# BasePCB.net
KiCad netlist of a schematic drawn in EAGLE
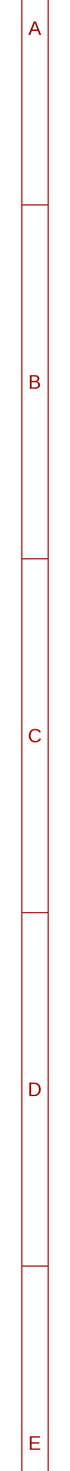
[diagram p0: schematic, sheet 1, part 1 of 2]
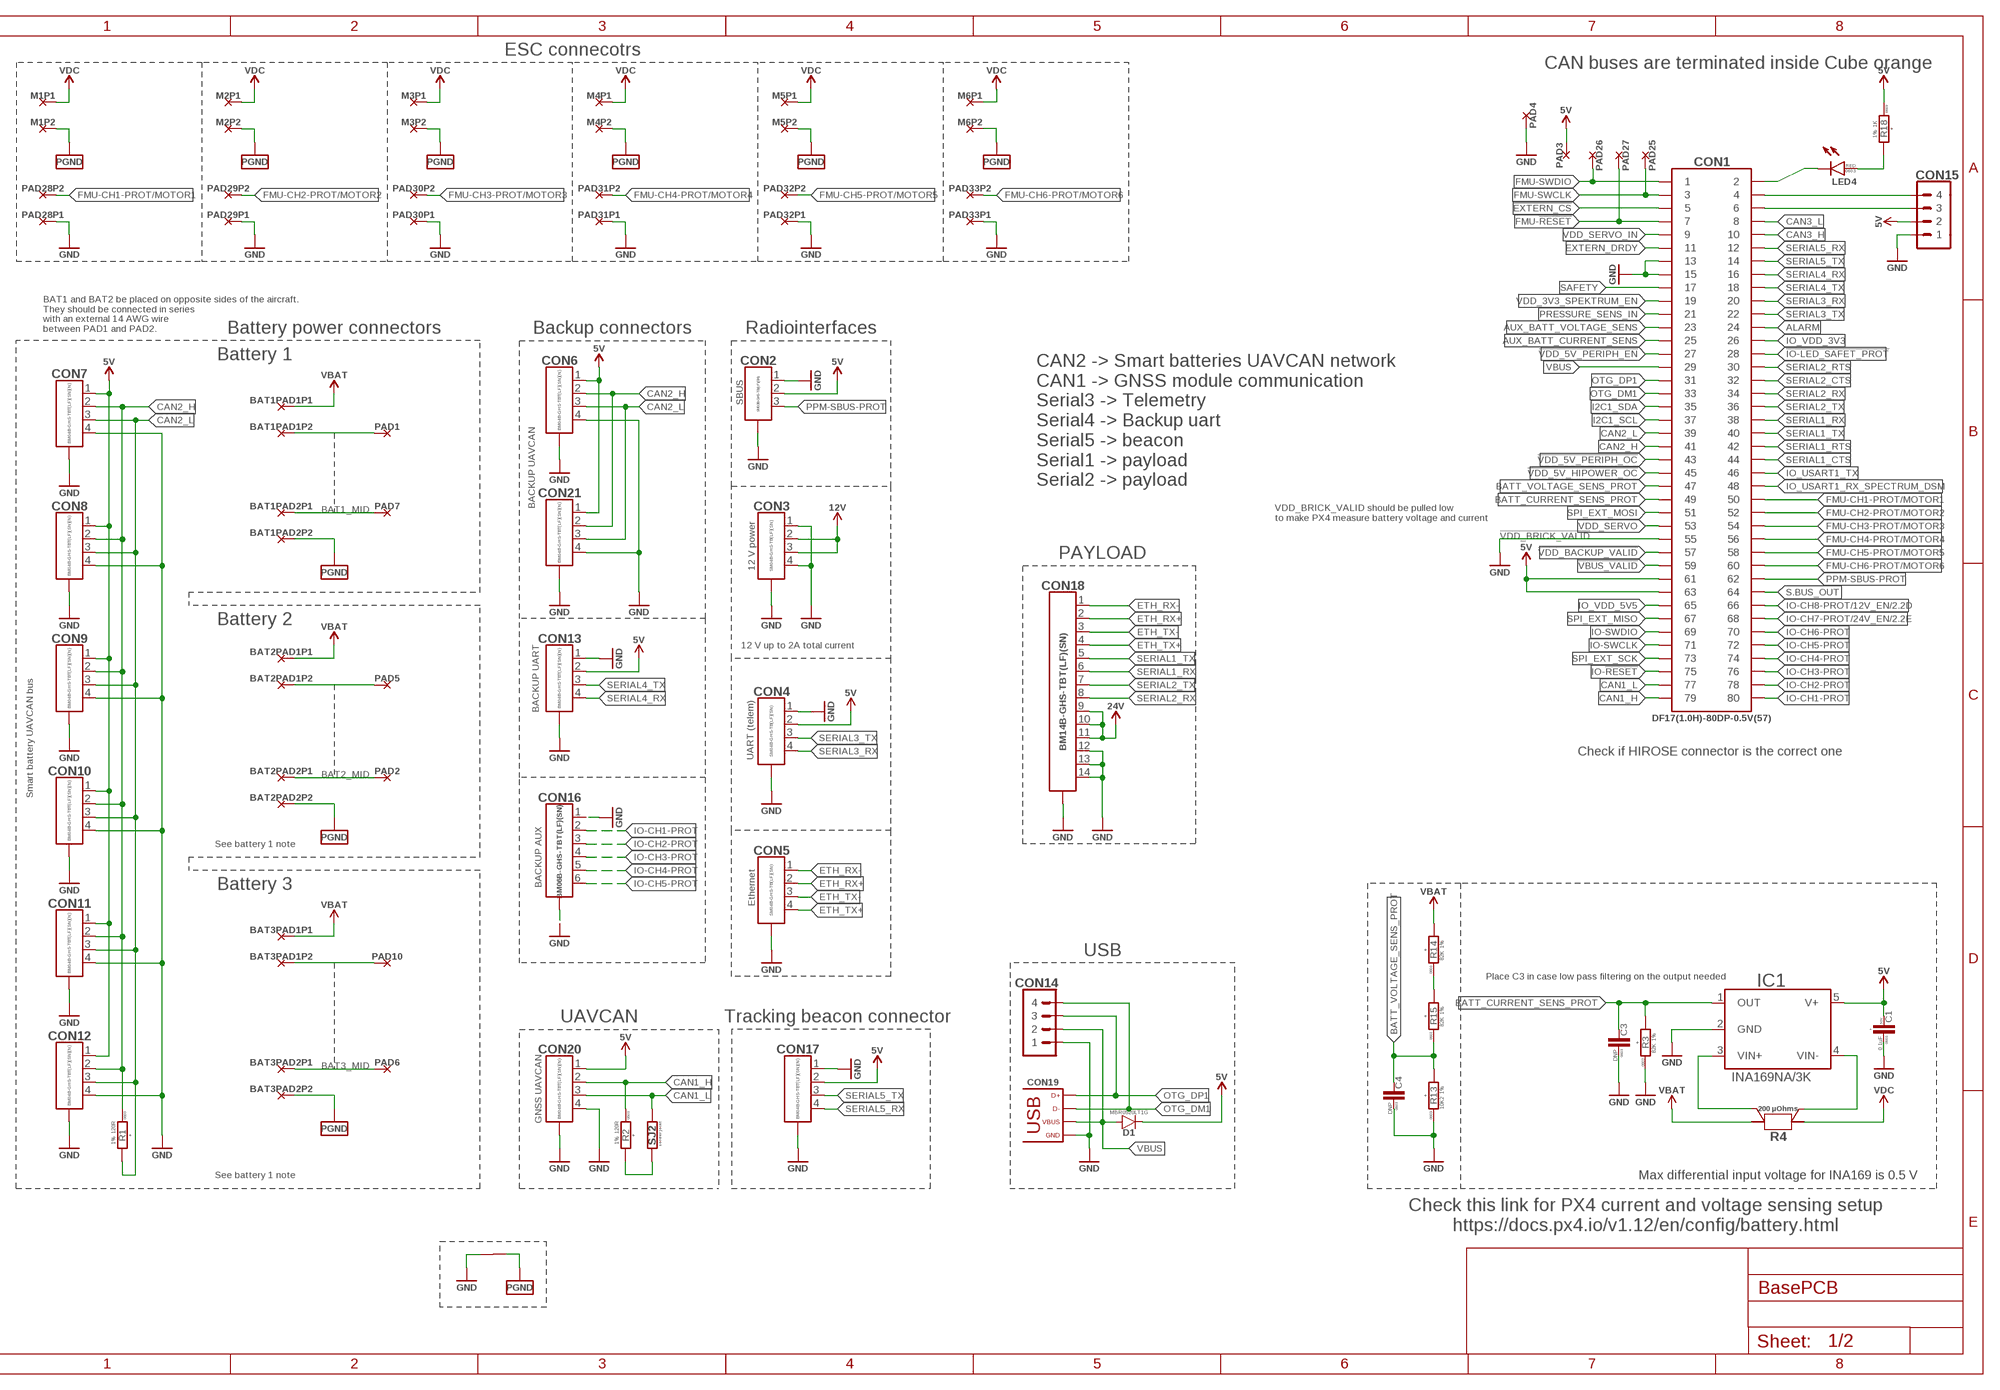
[diagram p1: schematic, sheet 1, part 2 of 2]
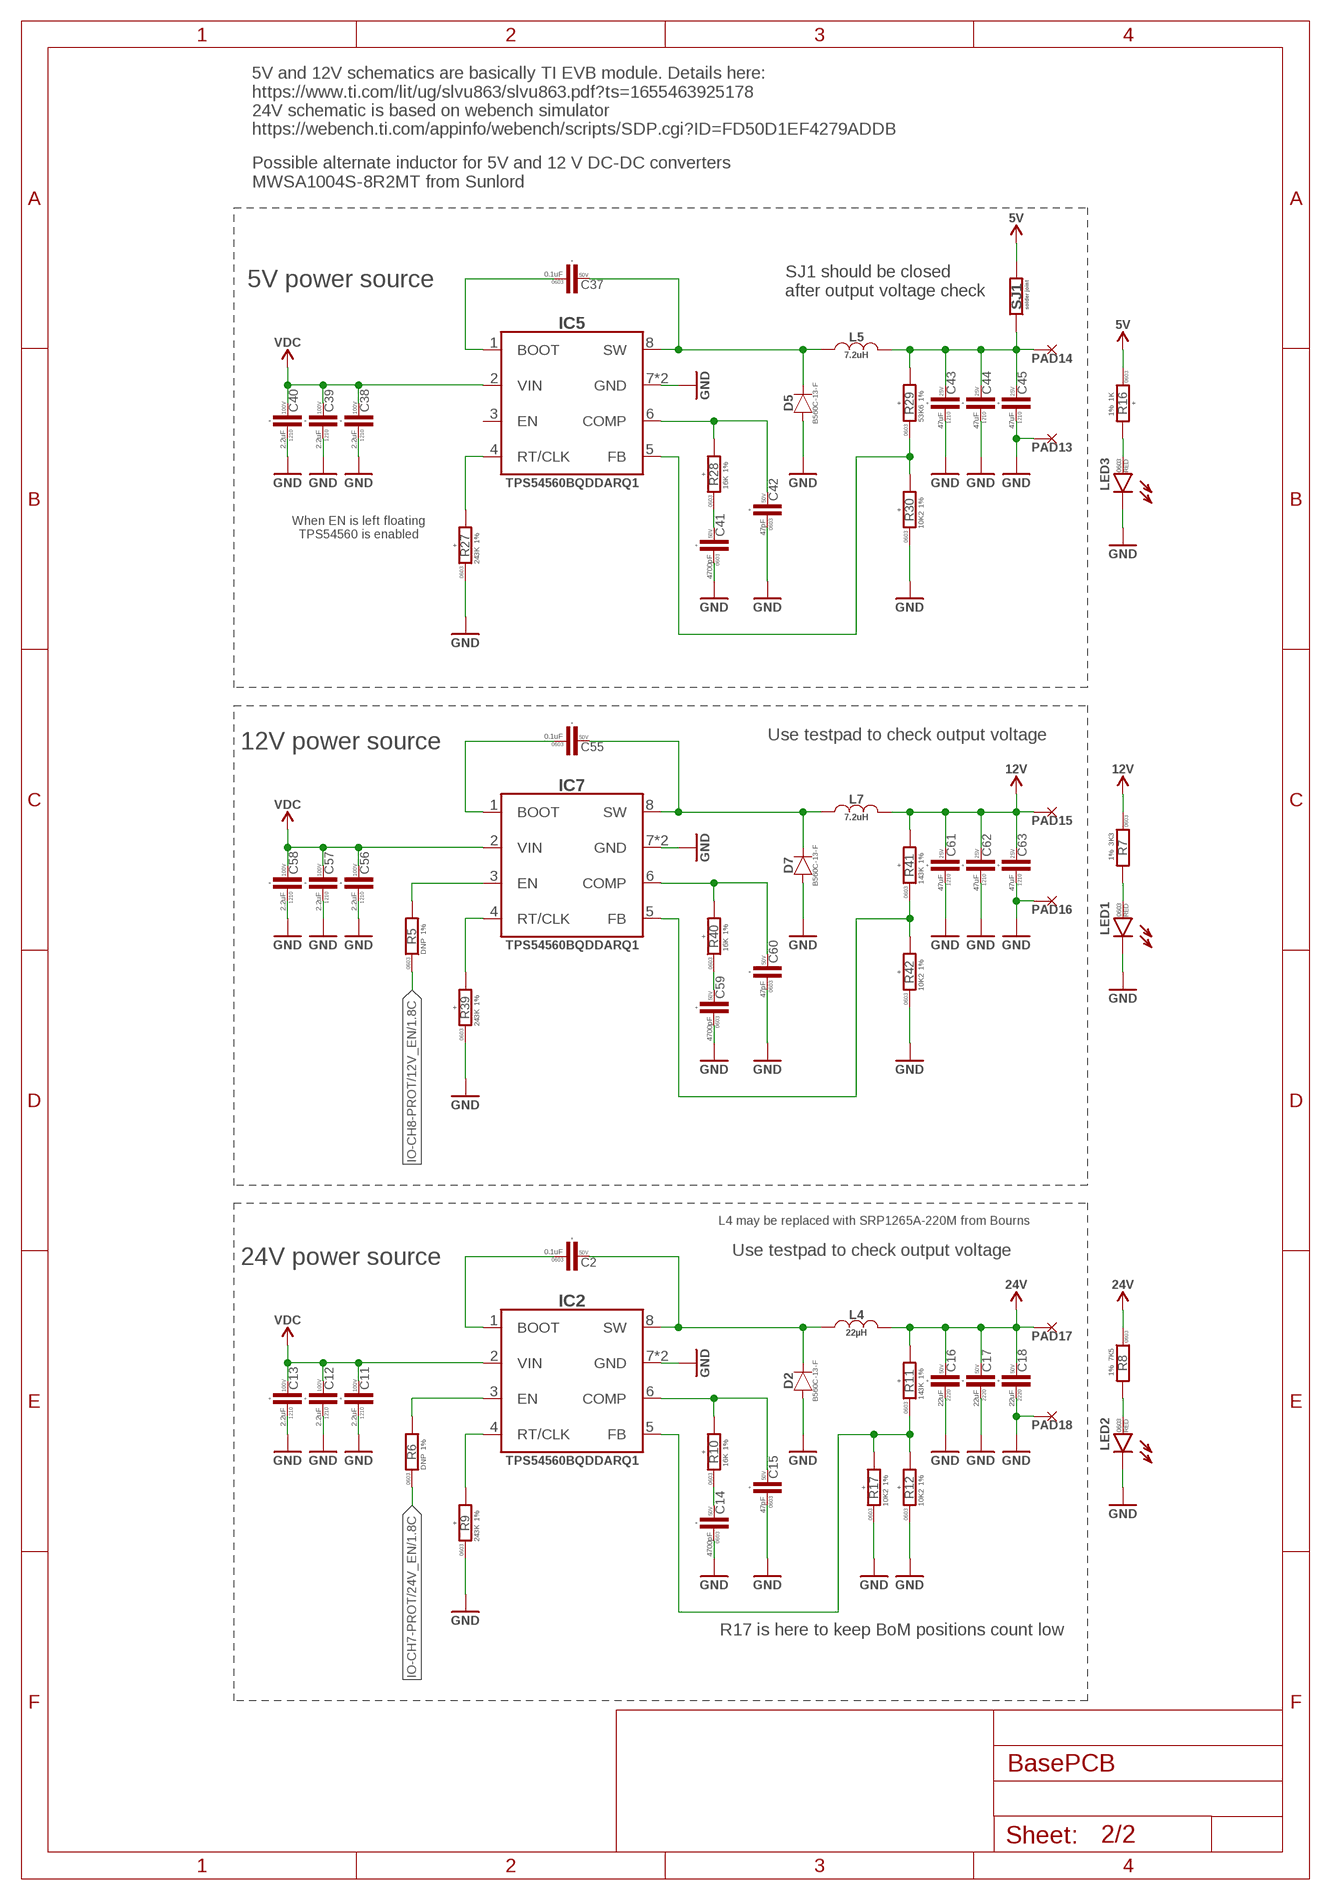
[diagram p2: schematic, sheet 2]

(export (version "E")
  (design (tool "Eeschema 10.0.6"))
  (components
    (comp (ref "C2")
      (value "0.1uF")
      (footprint "eagle-import:C0603")
      (fields
        (field (name "PACKAGE") "0603")
        (field (name "ALLOCATED") "+")
        (field (name "LCSC#") "C14663")
        (field (name "MANF") "YAGEO")
        (field (name "MANF#") "CC0603KRX7R9BB104")
        (field (name "VOLTAGE") "50V")
      )
      (libsource (lib "eagle-import") (part "C-0603"))
    )
    (comp (ref "C11")
      (value "2.2uF")
      (footprint "eagle-import:C1210")
      (fields
        (field (name "PACKAGE") "1210")
        (field (name "ALLOCATED") "+")
        (field (name "LCSC#") "C55151")
        (field (name "MANF") "Samsung Electro-Mechanics")
        (field (name "MANF#") "CL32B225KCJSNNE")
        (field (name "VOLTAGE") "100V")
      )
      (libsource (lib "eagle-import") (part "C-1210"))
    )
    (comp (ref "C12")
      (value "2.2uF")
      (footprint "eagle-import:C1210")
      (fields
        (field (name "PACKAGE") "1210")
        (field (name "ALLOCATED") "+")
        (field (name "LCSC#") "C55151")
        (field (name "MANF") "Samsung Electro-Mechanics")
        (field (name "MANF#") "CL32B225KCJSNNE")
        (field (name "VOLTAGE") "100V")
      )
      (libsource (lib "eagle-import") (part "C-1210"))
    )
    (comp (ref "C13")
      (value "2.2uF")
      (footprint "eagle-import:C1210")
      (fields
        (field (name "PACKAGE") "1210")
        (field (name "ALLOCATED") "+")
        (field (name "LCSC#") "C55151")
        (field (name "MANF") "Samsung Electro-Mechanics")
        (field (name "MANF#") "CL32B225KCJSNNE")
        (field (name "VOLTAGE") "100V")
      )
      (libsource (lib "eagle-import") (part "C-1210"))
    )
    (comp (ref "C14")
      (value "4700pF")
      (footprint "eagle-import:C0603")
      (fields
        (field (name "PACKAGE") "0603")
        (field (name "ALLOCATED") "+")
        (field (name "LCSC#") "C53987")
        (field (name "MANF") "FH(Guangdong Fenghua Advanced Tech)")
        (field (name "MANF#") "0603B472K500NT")
        (field (name "VOLTAGE") "50V")
      )
      (libsource (lib "eagle-import") (part "C-0603"))
    )
    (comp (ref "C15")
      (value "47pF")
      (footprint "eagle-import:C0603")
      (fields
        (field (name "PACKAGE") "0603")
        (field (name "ALLOCATED") "+")
        (field (name "LCSC#") "C1671")
        (field (name "MANF") "Samsung Electro-Mechanics")
        (field (name "MANF#") "CL10C470JB8NNNC")
        (field (name "VOLTAGE") "50V")
      )
      (libsource (lib "eagle-import") (part "C-0603"))
    )
    (comp (ref "C16")
      (value "22uF")
      (footprint "eagle-import:C2220")
      (fields
        (field (name "PACKAGE") "2220")
        (field (name "ALLOCATED") "+")
        (field (name "LCSC#") "C784103")
        (field (name "MANF") "PSA(Prosperity Dielectrics)")
        (field (name "MANF#") "FS55X226K500EHG")
        (field (name "VOLTAGE") "50V")
      )
      (libsource (lib "eagle-import") (part "C-C2220"))
    )
    (comp (ref "C17")
      (value "22uF")
      (footprint "eagle-import:C2220")
      (fields
        (field (name "PACKAGE") "2220")
        (field (name "ALLOCATED") "+")
        (field (name "LCSC#") "C784103")
        (field (name "MANF") "PSA(Prosperity Dielectrics)")
        (field (name "MANF#") "FS55X226K500EHG")
        (field (name "VOLTAGE") "50V")
      )
      (libsource (lib "eagle-import") (part "C-C2220"))
    )
    (comp (ref "C18")
      (value "22uF")
      (footprint "eagle-import:C2220")
      (fields
        (field (name "PACKAGE") "2220")
        (field (name "ALLOCATED") "+")
        (field (name "LCSC#") "C784103")
        (field (name "MANF") "PSA(Prosperity Dielectrics)")
        (field (name "MANF#") "FS55X226K500EHG")
        (field (name "VOLTAGE") "50V")
      )
      (libsource (lib "eagle-import") (part "C-C2220"))
    )
    (comp (ref "C37")
      (value "0.1uF")
      (footprint "eagle-import:C0603")
      (fields
        (field (name "PACKAGE") "0603")
        (field (name "ALLOCATED") "+")
        (field (name "LCSC#") "C14663")
        (field (name "MANF") "YAGEO")
        (field (name "MANF#") "CC0603KRX7R9BB104")
        (field (name "VOLTAGE") "50V")
      )
      (libsource (lib "eagle-import") (part "C-0603"))
    )
    (comp (ref "C38")
      (value "2.2uF")
      (footprint "eagle-import:C1210")
      (fields
        (field (name "PACKAGE") "1210")
        (field (name "ALLOCATED") "+")
        (field (name "LCSC#") "C55151")
        (field (name "MANF") "Samsung Electro-Mechanics")
        (field (name "MANF#") "CL32B225KCJSNNE")
        (field (name "VOLTAGE") "100V")
      )
      (libsource (lib "eagle-import") (part "C-1210"))
    )
    (comp (ref "C39")
      (value "2.2uF")
      (footprint "eagle-import:C1210")
      (fields
        (field (name "PACKAGE") "1210")
        (field (name "ALLOCATED") "+")
        (field (name "LCSC#") "C55151")
        (field (name "MANF") "Samsung Electro-Mechanics")
        (field (name "MANF#") "CL32B225KCJSNNE")
        (field (name "VOLTAGE") "100V")
      )
      (libsource (lib "eagle-import") (part "C-1210"))
    )
    (comp (ref "C40")
      (value "2.2uF")
      (footprint "eagle-import:C1210")
      (fields
        (field (name "PACKAGE") "1210")
        (field (name "ALLOCATED") "+")
        (field (name "LCSC#") "C55151")
        (field (name "MANF") "Samsung Electro-Mechanics")
        (field (name "MANF#") "CL32B225KCJSNNE")
        (field (name "VOLTAGE") "100V")
      )
      (libsource (lib "eagle-import") (part "C-1210"))
    )
    (comp (ref "C41")
      (value "4700pF")
      (footprint "eagle-import:C0603")
      (fields
        (field (name "PACKAGE") "0603")
        (field (name "ALLOCATED") "+")
        (field (name "LCSC#") "C53987")
        (field (name "MANF") "FH(Guangdong Fenghua Advanced Tech)")
        (field (name "MANF#") "0603B472K500NT")
        (field (name "VOLTAGE") "50V")
      )
      (libsource (lib "eagle-import") (part "C-0603"))
    )
    (comp (ref "C42")
      (value "47pF")
      (footprint "eagle-import:C0603")
      (fields
        (field (name "PACKAGE") "0603")
        (field (name "ALLOCATED") "+")
        (field (name "LCSC#") "C1671")
        (field (name "MANF") "Samsung Electro-Mechanics")
        (field (name "MANF#") "CL10C470JB8NNNC")
        (field (name "VOLTAGE") "50V")
      )
      (libsource (lib "eagle-import") (part "C-0603"))
    )
    (comp (ref "C43")
      (value "47uF")
      (footprint "eagle-import:C1210")
      (fields
        (field (name "PACKAGE") "1210")
        (field (name "ALLOCATED") "+")
        (field (name "LCSC#") "C90142")
        (field (name "MANF") "Taiyo Yuden")
        (field (name "MANF#") "TMK325ABJ476MM-P")
        (field (name "VOLTAGE") "25V")
      )
      (libsource (lib "eagle-import") (part "C-1210"))
    )
    (comp (ref "C44")
      (value "47uF")
      (footprint "eagle-import:C1210")
      (fields
        (field (name "PACKAGE") "1210")
        (field (name "ALLOCATED") "+")
        (field (name "LCSC#") "C90142")
        (field (name "MANF") "Taiyo Yuden")
        (field (name "MANF#") "TMK325ABJ476MM-P")
        (field (name "VOLTAGE") "25V")
      )
      (libsource (lib "eagle-import") (part "C-1210"))
    )
    (comp (ref "C45")
      (value "47uF")
      (footprint "eagle-import:C1210")
      (fields
        (field (name "PACKAGE") "1210")
        (field (name "ALLOCATED") "+")
        (field (name "LCSC#") "C90142")
        (field (name "MANF") "Taiyo Yuden")
        (field (name "MANF#") "TMK325ABJ476MM-P")
        (field (name "VOLTAGE") "25V")
      )
      (libsource (lib "eagle-import") (part "C-1210"))
    )
    (comp (ref "C55")
      (value "0.1uF")
      (footprint "eagle-import:C0603")
      (fields
        (field (name "PACKAGE") "0603")
        (field (name "ALLOCATED") "+")
        (field (name "LCSC#") "C14663")
        (field (name "MANF") "YAGEO")
        (field (name "MANF#") "CC0603KRX7R9BB104")
        (field (name "VOLTAGE") "50V")
      )
      (libsource (lib "eagle-import") (part "C-0603"))
    )
    (comp (ref "C56")
      (value "2.2uF")
      (footprint "eagle-import:C1210")
      (fields
        (field (name "PACKAGE") "1210")
        (field (name "ALLOCATED") "+")
        (field (name "LCSC#") "C55151")
        (field (name "MANF") "Samsung Electro-Mechanics")
        (field (name "MANF#") "CL32B225KCJSNNE")
        (field (name "VOLTAGE") "100V")
      )
      (libsource (lib "eagle-import") (part "C-1210"))
    )
    (comp (ref "C57")
      (value "2.2uF")
      (footprint "eagle-import:C1210")
      (fields
        (field (name "PACKAGE") "1210")
        (field (name "ALLOCATED") "+")
        (field (name "LCSC#") "C55151")
        (field (name "MANF") "Samsung Electro-Mechanics")
        (field (name "MANF#") "CL32B225KCJSNNE")
        (field (name "VOLTAGE") "100V")
      )
      (libsource (lib "eagle-import") (part "C-1210"))
    )
    (comp (ref "C58")
      (value "2.2uF")
      (footprint "eagle-import:C1210")
      (fields
        (field (name "PACKAGE") "1210")
        (field (name "ALLOCATED") "+")
        (field (name "LCSC#") "C55151")
        (field (name "MANF") "Samsung Electro-Mechanics")
        (field (name "MANF#") "CL32B225KCJSNNE")
        (field (name "VOLTAGE") "100V")
      )
      (libsource (lib "eagle-import") (part "C-1210"))
    )
    (comp (ref "C59")
      (value "4700pF")
      (footprint "eagle-import:C0603")
      (fields
        (field (name "PACKAGE") "0603")
        (field (name "ALLOCATED") "+")
        (field (name "LCSC#") "C53987")
        (field (name "MANF") "FH(Guangdong Fenghua Advanced Tech)")
        (field (name "MANF#") "0603B472K500NT")
        (field (name "VOLTAGE") "50V")
      )
      (libsource (lib "eagle-import") (part "C-0603"))
    )
    (comp (ref "C60")
      (value "47pF")
      (footprint "eagle-import:C0603")
      (fields
        (field (name "PACKAGE") "0603")
        (field (name "ALLOCATED") "+")
        (field (name "LCSC#") "C1620")
        (field (name "MANF") "FH(Guangdong Fenghua Advanced Tech)")
        (field (name "MANF#") "0603B471K500NT")
        (field (name "VOLTAGE") "50V")
      )
      (libsource (lib "eagle-import") (part "C-0603"))
    )
    (comp (ref "C61")
      (value "47uF")
      (footprint "eagle-import:C1210")
      (fields
        (field (name "PACKAGE") "1210")
        (field (name "ALLOCATED") "+")
        (field (name "LCSC#") "C90142")
        (field (name "MANF") "Taiyo Yuden")
        (field (name "MANF#") "TMK325ABJ476MM-P")
        (field (name "VOLTAGE") "25V")
      )
      (libsource (lib "eagle-import") (part "C-1210"))
    )
    (comp (ref "C62")
      (value "47uF")
      (footprint "eagle-import:C1210")
      (fields
        (field (name "PACKAGE") "1210")
        (field (name "ALLOCATED") "+")
        (field (name "LCSC#") "C90142")
        (field (name "MANF") "Taiyo Yuden")
        (field (name "MANF#") "TMK325ABJ476MM-P")
        (field (name "VOLTAGE") "25V")
      )
      (libsource (lib "eagle-import") (part "C-1210"))
    )
    (comp (ref "C63")
      (value "47uF")
      (footprint "eagle-import:C1210")
      (fields
        (field (name "PACKAGE") "1210")
        (field (name "ALLOCATED") "+")
        (field (name "LCSC#") "C90142")
        (field (name "MANF") "Taiyo Yuden")
        (field (name "MANF#") "TMK325ABJ476MM-P")
        (field (name "VOLTAGE") "25V")
      )
      (libsource (lib "eagle-import") (part "C-1210"))
    )
    (comp (ref "D2")
      (value "B560C")
      (footprint "eagle-import:DO-214AB(SMC)")
      (fields (field (name "MANF#") "B560C-13-F") (field (name "MANF") "Diodes Incorporated"))
      (libsource (lib "eagle-import") (part "B560C"))
    )
    (comp (ref "D5")
      (value "B560C")
      (footprint "eagle-import:DO-214AB(SMC)")
      (fields (field (name "MANF#") "B560C-13-F") (field (name "MANF") "Diodes Incorporated"))
      (libsource (lib "eagle-import") (part "B560C"))
    )
    (comp (ref "D7")
      (value "B560C")
      (footprint "eagle-import:DO-214AB(SMC)")
      (fields (field (name "MANF#") "B560C-13-F") (field (name "MANF") "Diodes Incorporated"))
      (libsource (lib "eagle-import") (part "B560C"))
    )
    (comp (ref "IC2")
      (value "TPS54560B")
      (footprint "eagle-import:SOIC8-POWERPAD")
      (fields (field (name "MANF#") "TPS54560BQDDARQ1") (field (name "MANF") "Texas Instruments"))
      (libsource (lib "eagle-import") (part "TPS54560B"))
    )
    (comp (ref "IC5")
      (value "TPS54560B")
      (footprint "eagle-import:SOIC8-POWERPAD")
      (fields (field (name "MANF#") "TPS54560BQDDARQ1") (field (name "MANF") "Texas Instruments"))
      (libsource (lib "eagle-import") (part "TPS54560B"))
    )
    (comp (ref "IC7")
      (value "TPS54560B")
      (footprint "eagle-import:SOIC8-POWERPAD")
      (fields (field (name "MANF#") "TPS54560BQDDARQ1") (field (name "MANF") "Texas Instruments"))
      (libsource (lib "eagle-import") (part "TPS54560B"))
    )
    (comp (ref "L4")
      (value "22µH")
      (footprint "eagle-import:MWSA1206S")
      (fields (field (name "MANF") "SUNLORD"))
      (libsource (lib "eagle-import") (part "22µH-MWSA1206S"))
    )
    (comp (ref "L5")
      (value "7.2uH")
      (footprint "eagle-import:1064")
      (fields (field (name "MANF") "Wurth Elektronik"))
      (libsource (lib "eagle-import") (part "7.2µH-1064"))
    )
    (comp (ref "L7")
      (value "7.2uH")
      (footprint "eagle-import:1064")
      (fields (field (name "MANF") "Wurth Elektronik"))
      (libsource (lib "eagle-import") (part "7.2µH-1064"))
    )
    (comp (ref "LED1")
      (value "LED-0603")
      (footprint "eagle-import:LED0603")
      (fields
        (field (name "PACKAGE") "0603")
        (field (name "COLOR") "RED")
        (field (name "LCSC#") "C2286")
        (field (name "MANF") "Hubei KENTO Elec")
        (field (name "MANF#") "KT-0603R")
      )
      (libsource (lib "eagle-import") (part "LED-0603"))
    )
    (comp (ref "LED2")
      (value "LED-0603")
      (footprint "eagle-import:LED0603")
      (fields
        (field (name "PACKAGE") "0603")
        (field (name "COLOR") "RED")
        (field (name "LCSC#") "C2286")
        (field (name "MANF") "Hubei KENTO Elec")
        (field (name "MANF#") "KT-0603R")
      )
      (libsource (lib "eagle-import") (part "LED-0603"))
    )
    (comp (ref "LED3")
      (value "LED-0603")
      (footprint "eagle-import:LED0603")
      (fields
        (field (name "PACKAGE") "0603")
        (field (name "COLOR") "RED")
        (field (name "LCSC#") "C2286")
        (field (name "MANF") "Hubei KENTO Elec")
        (field (name "MANF#") "KT-0603R")
      )
      (libsource (lib "eagle-import") (part "LED-0603"))
    )
    (comp (ref "PAD13")
      (value "PAD-S_2X2")
      (footprint "eagle-import:2х2")
      (libsource (lib "eagle-import") (part "PAD-S_2X2"))
    )
    (comp (ref "PAD14")
      (value "PAD-S_2X2")
      (footprint "eagle-import:2х2")
      (libsource (lib "eagle-import") (part "PAD-S_2X2"))
    )
    (comp (ref "PAD15")
      (value "PAD-S_2X2")
      (footprint "eagle-import:2х2")
      (libsource (lib "eagle-import") (part "PAD-S_2X2"))
    )
    (comp (ref "PAD16")
      (value "PAD-S_2X2")
      (footprint "eagle-import:2х2")
      (libsource (lib "eagle-import") (part "PAD-S_2X2"))
    )
    (comp (ref "PAD17")
      (value "PAD-S_2X2")
      (footprint "eagle-import:2х2")
      (libsource (lib "eagle-import") (part "PAD-S_2X2"))
    )
    (comp (ref "PAD18")
      (value "PAD-S_2X2")
      (footprint "eagle-import:2х2")
      (libsource (lib "eagle-import") (part "PAD-S_2X2"))
    )
    (comp (ref "R5")
      (value "DNP")
      (footprint "eagle-import:R0603")
      (fields (field (name "PACKAGE") "0603") (field (name "TOLERANCE") "1%"))
      (libsource (lib "eagle-import") (part "R-0603-1%"))
    )
    (comp (ref "R6")
      (value "DNP")
      (footprint "eagle-import:R0603")
      (fields (field (name "PACKAGE") "0603") (field (name "TOLERANCE") "1%"))
      (libsource (lib "eagle-import") (part "R-0603-1%"))
    )
    (comp (ref "R7")
      (value "3K3")
      (footprint "eagle-import:R0603")
      (fields
        (field (name "PACKAGE") "0603")
        (field (name "TOLERANCE") "1%")
        (field (name "LCSC#") "C22978")
        (field (name "MANF") "UNI-ROYAL(Uniroyal Elec)")
        (field (name "MANF#") "0603WAF3301T5E")
      )
      (libsource (lib "eagle-import") (part "R-0603-1%"))
    )
    (comp (ref "R8")
      (value "7K5")
      (footprint "eagle-import:R0603")
      (fields
        (field (name "PACKAGE") "0603")
        (field (name "TOLERANCE") "1%")
        (field (name "LCSC#") "C23234")
        (field (name "MANF") "UNI-ROYAL(Uniroyal Elec)")
        (field (name "MANF#") "0603WAF7501T5E")
      )
      (libsource (lib "eagle-import") (part "R-0603-1%"))
    )
    (comp (ref "R9")
      (value "243K")
      (footprint "eagle-import:R0603")
      (fields
        (field (name "PACKAGE") "0603")
        (field (name "TOLERANCE") "1%")
        (field (name "ALLOCATED") "+")
        (field (name "LCSC#") "C23351")
        (field (name "MANF") "UNI-ROYAL(Uniroyal Elec)")
        (field (name "MANF#") "0603WAF2433T5E")
      )
      (libsource (lib "eagle-import") (part "R-0603-1%"))
    )
    (comp (ref "R10")
      (value "16K")
      (footprint "eagle-import:R0603")
      (fields
        (field (name "PACKAGE") "0603")
        (field (name "TOLERANCE") "1%")
        (field (name "ALLOCATED") "+")
        (field (name "LCSC#") "C4210")
        (field (name "MANF") "UNI-ROYAL(Uniroyal Elec)")
        (field (name "MANF#") "0603WAF1602T5E")
      )
      (libsource (lib "eagle-import") (part "R-0603-1%"))
    )
    (comp (ref "R11")
      (value "143K")
      (footprint "eagle-import:R0603")
      (fields
        (field (name "PACKAGE") "0603")
        (field (name "TOLERANCE") "1%")
        (field (name "ALLOCATED") "+")
        (field (name "LCSC#") "C22877")
        (field (name "MANF") "UNI-ROYAL(Uniroyal Elec)")
        (field (name "MANF#") "0603WAF1433T5E")
      )
      (libsource (lib "eagle-import") (part "R-0603-1%"))
    )
    (comp (ref "R12")
      (value "10K2")
      (footprint "eagle-import:R0603")
      (fields
        (field (name "PACKAGE") "0603")
        (field (name "TOLERANCE") "1%")
        (field (name "ALLOCATED") "+")
        (field (name "LCSC#") "C22772")
        (field (name "MANF") "UNI-ROYAL(Uniroyal Elec)")
        (field (name "MANF#") "0603WAF1022T5E")
      )
      (libsource (lib "eagle-import") (part "R-0603-1%"))
    )
    (comp (ref "R16")
      (value "1K")
      (footprint "eagle-import:R0603")
      (fields
        (field (name "PACKAGE") "0603")
        (field (name "TOLERANCE") "1%")
        (field (name "ALLOCATED") "+")
        (field (name "LCSC#") "C21190")
        (field (name "MANF") "UNI-ROYAL(Uniroyal Elec)")
        (field (name "MANF#") "0603WAF1001T5E")
      )
      (libsource (lib "eagle-import") (part "R-0603-1%"))
    )
    (comp (ref "R17")
      (value "10K2")
      (footprint "eagle-import:R0603")
      (fields
        (field (name "PACKAGE") "0603")
        (field (name "TOLERANCE") "1%")
        (field (name "ALLOCATED") "+")
        (field (name "LCSC#") "C22772")
        (field (name "MANF") "UNI-ROYAL(Uniroyal Elec)")
        (field (name "MANF#") "0603WAF1022T5E")
      )
      (libsource (lib "eagle-import") (part "R-0603-1%"))
    )
    (comp (ref "R27")
      (value "243K")
      (footprint "eagle-import:R0603")
      (fields
        (field (name "PACKAGE") "0603")
        (field (name "TOLERANCE") "1%")
        (field (name "ALLOCATED") "+")
        (field (name "LCSC#") "C23351")
        (field (name "MANF") "UNI-ROYAL(Uniroyal Elec)")
        (field (name "MANF#") "0603WAF2433T5E")
      )
      (libsource (lib "eagle-import") (part "R-0603-1%"))
    )
    (comp (ref "R28")
      (value "16K")
      (footprint "eagle-import:R0603")
      (fields
        (field (name "PACKAGE") "0603")
        (field (name "TOLERANCE") "1%")
        (field (name "ALLOCATED") "+")
        (field (name "LCSC#") "C4210")
        (field (name "MANF") "UNI-ROYAL(Uniroyal Elec)")
        (field (name "MANF#") "0603WAF1602T5E")
      )
      (libsource (lib "eagle-import") (part "R-0603-1%"))
    )
    (comp (ref "R29")
      (value "53K6")
      (footprint "eagle-import:R0603")
      (fields
        (field (name "PACKAGE") "0603")
        (field (name "TOLERANCE") "1%")
        (field (name "ALLOCATED") "+")
        (field (name "LCSC#") "C23074")
        (field (name "MANF") "UNI-ROYAL(Uniroyal Elec)")
        (field (name "MANF#") "0603WAF5362T5E")
      )
      (libsource (lib "eagle-import") (part "R-0603-1%"))
    )
    (comp (ref "R30")
      (value "10K2")
      (footprint "eagle-import:R0603")
      (fields
        (field (name "PACKAGE") "0603")
        (field (name "TOLERANCE") "1%")
        (field (name "ALLOCATED") "+")
        (field (name "LCSC#") "C22772")
        (field (name "MANF") "UNI-ROYAL(Uniroyal Elec)")
        (field (name "MANF#") "0603WAF1022T5E")
      )
      (libsource (lib "eagle-import") (part "R-0603-1%"))
    )
    (comp (ref "R39")
      (value "243K")
      (footprint "eagle-import:R0603")
      (fields
        (field (name "PACKAGE") "0603")
        (field (name "TOLERANCE") "1%")
        (field (name "ALLOCATED") "+")
        (field (name "LCSC#") "C23351")
        (field (name "MANF") "UNI-ROYAL(Uniroyal Elec)")
        (field (name "MANF#") "0603WAF2433T5E")
      )
      (libsource (lib "eagle-import") (part "R-0603-1%"))
    )
    (comp (ref "R40")
      (value "16K")
      (footprint "eagle-import:R0603")
      (fields
        (field (name "PACKAGE") "0603")
        (field (name "TOLERANCE") "1%")
        (field (name "ALLOCATED") "+")
        (field (name "LCSC#") "C4210")
        (field (name "MANF") "UNI-ROYAL(Uniroyal Elec)")
        (field (name "MANF#") "0603WAF1602T5E")
      )
      (libsource (lib "eagle-import") (part "R-0603-1%"))
    )
    (comp (ref "R41")
      (value "143K")
      (footprint "eagle-import:R0603")
      (fields
        (field (name "PACKAGE") "0603")
        (field (name "TOLERANCE") "1%")
        (field (name "ALLOCATED") "+")
        (field (name "LCSC#") "C22877")
        (field (name "MANF") "UNI-ROYAL(Uniroyal Elec)")
        (field (name "MANF#") "0603WAF1433T5E")
      )
      (libsource (lib "eagle-import") (part "R-0603-1%"))
    )
    (comp (ref "R42")
      (value "10K2")
      (footprint "eagle-import:R0603")
      (fields
        (field (name "PACKAGE") "0603")
        (field (name "TOLERANCE") "1%")
        (field (name "ALLOCATED") "+")
        (field (name "LCSC#") "C22772")
        (field (name "MANF") "UNI-ROYAL(Uniroyal Elec)")
        (field (name "MANF#") "0603WAF1022T5E")
      )
      (libsource (lib "eagle-import") (part "R-0603-1%"))
    )
    (comp (ref "SJ1")
      (value "SOLDER_JOINT-SJ1")
      (footprint "eagle-import:RES_0")
      (libsource (lib "eagle-import") (part "SOLDER_JOINT-SJ1"))
    )
    (comp (ref "BAT1PAD1")
      (value "PAD_PAIR-4X10")
      (footprint "eagle-import:4X10_PAIR")
      (libsource (lib "eagle-import") (part "PAD_PAIR-4X10"))
    )
    (comp (ref "BAT1PAD2")
      (value "PAD_PAIR-4X10")
      (footprint "eagle-import:4X10_PAIR")
      (libsource (lib "eagle-import") (part "PAD_PAIR-4X10"))
    )
    (comp (ref "BAT2PAD1")
      (value "PAD_PAIR-4X10")
      (footprint "eagle-import:4X10_PAIR")
      (libsource (lib "eagle-import") (part "PAD_PAIR-4X10"))
    )
    (comp (ref "BAT2PAD2")
      (value "PAD_PAIR-4X10")
      (footprint "eagle-import:4X10_PAIR")
      (libsource (lib "eagle-import") (part "PAD_PAIR-4X10"))
    )
    (comp (ref "BAT3PAD1")
      (value "PAD_PAIR-4X10")
      (footprint "eagle-import:4X10_PAIR")
      (libsource (lib "eagle-import") (part "PAD_PAIR-4X10"))
    )
    (comp (ref "BAT3PAD2")
      (value "PAD_PAIR-4X10")
      (footprint "eagle-import:4X10_PAIR")
      (libsource (lib "eagle-import") (part "PAD_PAIR-4X10"))
    )
    (comp (ref "C1")
      (value "0.1uF")
      (footprint "eagle-import:C0603")
      (fields
        (field (name "PACKAGE") "0603")
        (field (name "ALLOCATED") "+")
        (field (name "LCSC#") "C14663")
        (field (name "MANF") "YAGEO")
        (field (name "MANF#") "CC0603KRX7R9BB104")
        (field (name "VOLTAGE") "50V")
      )
      (libsource (lib "eagle-import") (part "C-0603"))
    )
    (comp (ref "C3")
      (value "DNP")
      (footprint "eagle-import:C0603")
      (fields (field (name "PACKAGE") "0603"))
      (libsource (lib "eagle-import") (part "C-0603"))
    )
    (comp (ref "C4")
      (value "DNP")
      (footprint "eagle-import:C0603")
      (fields (field (name "PACKAGE") "0603"))
      (libsource (lib "eagle-import") (part "C-0603"))
    )
    (comp (ref "CON1")
      (value "CON-80P-DF17(1.0H)-80DP-0.5V")
      (footprint "eagle-import:DF17(1.0H)-80DP-0.5V")
      (fields (field (name "MANF#") "DF17(1.0H)-80DP-0.5V(57)") (field (name "MANF") "HIROSE"))
      (libsource (lib "eagle-import") (part "CON-80P-DF17(1.0H)-80DP-0.5V"))
    )
    (comp (ref "CON2")
      (value "CON-3P-TABS-JST-GH-SIDE")
      (footprint "eagle-import:SM03B-GHS-TB")
      (fields (field (name "MANF#") "SM03B-GHS-TB(LF)(SN) ") (field (name "MANF") "JST Sales America Inc"))
      (libsource (lib "eagle-import") (part "CON-3P-TABS-JST-GH-SIDE"))
    )
    (comp (ref "CON3")
      (value "CON-4P-TABS-JST-GH-SIDE")
      (footprint "eagle-import:SM04B-GHS-TB")
      (fields (field (name "MANF#") "SM04B-GHS-TB(LF)(SN)") (field (name "MANF") "JST Sales America Inc"))
      (libsource (lib "eagle-import") (part "CON-4P-TABS-JST-GH-SIDE"))
    )
    (comp (ref "CON4")
      (value "CON-4P-TABS-JST-GH-SIDE")
      (footprint "eagle-import:SM04B-GHS-TB")
      (fields (field (name "MANF#") "SM04B-GHS-TB(LF)(SN)") (field (name "MANF") "JST Sales America Inc"))
      (libsource (lib "eagle-import") (part "CON-4P-TABS-JST-GH-SIDE"))
    )
    (comp (ref "CON5")
      (value "CON-4P-TABS-JST-GH-SIDE")
      (footprint "eagle-import:SM04B-GHS-TB")
      (fields (field (name "MANF#") "SM04B-GHS-TB(LF)(SN)") (field (name "MANF") "JST Sales America Inc"))
      (libsource (lib "eagle-import") (part "CON-4P-TABS-JST-GH-SIDE"))
    )
    (comp (ref "CON6")
      (value "CON-4P-TABS-JST-GH-TOP")
      (footprint "eagle-import:BM04B-GHS-TB")
      (fields (field (name "MANF#") "BM04B-GHS-TBT(LF)(SN)(N)") (field (name "MANF") "JST Sales America Inc"))
      (libsource (lib "eagle-import") (part "CON-4P-TABS-JST-GH-TOP"))
    )
    (comp (ref "CON7")
      (value "CON-4P-TABS-JST-GH-TOP")
      (footprint "eagle-import:BM04B-GHS-TB")
      (fields (field (name "MANF#") "BM04B-GHS-TBT(LF)(SN)(N)") (field (name "MANF") "JST Sales America Inc"))
      (libsource (lib "eagle-import") (part "CON-4P-TABS-JST-GH-TOP"))
    )
    (comp (ref "CON8")
      (value "CON-4P-TABS-JST-GH-TOP")
      (footprint "eagle-import:BM04B-GHS-TB")
      (fields (field (name "MANF#") "BM04B-GHS-TBT(LF)(SN)(N)") (field (name "MANF") "JST Sales America Inc"))
      (libsource (lib "eagle-import") (part "CON-4P-TABS-JST-GH-TOP"))
    )
    (comp (ref "CON9")
      (value "CON-4P-TABS-JST-GH-TOP")
      (footprint "eagle-import:BM04B-GHS-TB")
      (fields (field (name "MANF#") "BM04B-GHS-TBT(LF)(SN)(N)") (field (name "MANF") "JST Sales America Inc"))
      (libsource (lib "eagle-import") (part "CON-4P-TABS-JST-GH-TOP"))
    )
    (comp (ref "CON10")
      (value "CON-4P-TABS-JST-GH-TOP")
      (footprint "eagle-import:BM04B-GHS-TB")
      (fields (field (name "MANF#") "BM04B-GHS-TBT(LF)(SN)(N)") (field (name "MANF") "JST Sales America Inc"))
      (libsource (lib "eagle-import") (part "CON-4P-TABS-JST-GH-TOP"))
    )
    (comp (ref "CON11")
      (value "CON-4P-TABS-JST-GH-TOP")
      (footprint "eagle-import:BM04B-GHS-TB")
      (fields (field (name "MANF#") "BM04B-GHS-TBT(LF)(SN)(N)") (field (name "MANF") "JST Sales America Inc"))
      (libsource (lib "eagle-import") (part "CON-4P-TABS-JST-GH-TOP"))
    )
    (comp (ref "CON12")
      (value "CON-4P-TABS-JST-GH-TOP")
      (footprint "eagle-import:BM04B-GHS-TB")
      (fields (field (name "MANF#") "BM04B-GHS-TBT(LF)(SN)(N)") (field (name "MANF") "JST Sales America Inc"))
      (libsource (lib "eagle-import") (part "CON-4P-TABS-JST-GH-TOP"))
    )
    (comp (ref "CON13")
      (value "CON-4P-TABS-JST-GH-TOP")
      (footprint "eagle-import:BM04B-GHS-TB")
      (fields (field (name "MANF#") "BM04B-GHS-TBT(LF)(SN)(N)") (field (name "MANF") "JST Sales America Inc"))
      (libsource (lib "eagle-import") (part "CON-4P-TABS-JST-GH-TOP"))
    )
    (comp (ref "CON14")
      (value "PINHEAD_1X04-2.54")
      (footprint "eagle-import:1X04-PTH-2.54")
      (libsource (lib "eagle-import") (part "PINHEAD_1X04-2.54"))
    )
    (comp (ref "CON15")
      (value "PINHEAD_1X04-2.54")
      (footprint "eagle-import:1X04-PTH-2.54")
      (libsource (lib "eagle-import") (part "PINHEAD_1X04-2.54"))
    )
    (comp (ref "CON16")
      (value "CON-6P-TABS-JST-GH-TOP")
      (footprint "eagle-import:BM06B-GHS-TBT")
      (fields (field (name "MANF#") "BM06B-GHS-TBT(LF)(SN) ") (field (name "MANF") "JST Sales America Inc"))
      (libsource (lib "eagle-import") (part "CON-6P-TABS-JST-GH-TOP"))
    )
    (comp (ref "CON17")
      (value "CON-4P-TABS-JST-GH-TOP")
      (footprint "eagle-import:BM04B-GHS-TB")
      (fields (field (name "MANF#") "BM04B-GHS-TBT(LF)(SN)(N)") (field (name "MANF") "JST Sales America Inc"))
      (libsource (lib "eagle-import") (part "CON-4P-TABS-JST-GH-TOP"))
    )
    (comp (ref "CON18")
      (value "CON-14P-TABS-JST-GH-TOP")
      (footprint "eagle-import:BM14B-GHS-TBT")
      (fields (field (name "MANF#") "BM14B-GHS-TBT(LF)(SN)") (field (name "MANF") "JST Sales America"))
      (libsource (lib "eagle-import") (part "CON-14P-TABS-JST-GH-TOP"))
    )
    (comp (ref "CON19")
      (value "USB-TYPE-C-VERT-PROD")
      (footprint "eagle-import:2047110001-PROD")
      (libsource (lib "eagle-import") (part "USB-TYPE-C-VERT-PROD"))
    )
    (comp (ref "CON20")
      (value "CON-4P-TABS-JST-GH-TOP")
      (footprint "eagle-import:BM04B-GHS-TB")
      (fields (field (name "MANF#") "BM04B-GHS-TBT(LF)(SN)(N)") (field (name "MANF") "JST Sales America Inc"))
      (libsource (lib "eagle-import") (part "CON-4P-TABS-JST-GH-TOP"))
    )
    (comp (ref "CON21")
      (value "CON-4P-TABS-JST-GH-TOP")
      (footprint "eagle-import:BM04B-GHS-TB")
      (fields (field (name "MANF#") "BM04B-GHS-TBT(LF)(SN)(N)") (field (name "MANF") "JST Sales America Inc"))
      (libsource (lib "eagle-import") (part "CON-4P-TABS-JST-GH-TOP"))
    )
    (comp (ref "D1")
      (value "MBR0520L-SOD123")
      (footprint "eagle-import:SOD123")
      (fields (field (name "MANF#") "MBR0520LT1G") (field (name "MANF") "ON Semiconductor"))
      (libsource (lib "eagle-import") (part "MBR0520L-SOD123"))
    )
    (comp (ref "IC1")
      (value "INA169")
      (footprint "eagle-import:SOT23-5")
      (fields (field (name "MANF") "Texas Instruments"))
      (libsource (lib "eagle-import") (part "INA169"))
    )
    (comp (ref "J1")
      (value "CONNECTION-SMD-BIG")
      (footprint "eagle-import:CONNECTION_BIG")
      (libsource (lib "eagle-import") (part "CONNECTION-SMD-BIG"))
    )
    (comp (ref "LED4")
      (value "LED-0603")
      (footprint "eagle-import:LED0603")
      (fields
        (field (name "PACKAGE") "0603")
        (field (name "COLOR") "RED")
        (field (name "LCSC#") "C2286")
        (field (name "MANF") "Hubei KENTO Elec")
        (field (name "MANF#") "KT-0603R")
      )
      (libsource (lib "eagle-import") (part "LED-0603"))
    )
    (comp (ref "M1")
      (value "PAD_PAIR-4X10")
      (footprint "eagle-import:4X10_PAIR")
      (libsource (lib "eagle-import") (part "PAD_PAIR-4X10"))
    )
    (comp (ref "M2")
      (value "PAD_PAIR-4X10")
      (footprint "eagle-import:4X10_PAIR")
      (libsource (lib "eagle-import") (part "PAD_PAIR-4X10"))
    )
    (comp (ref "M3")
      (value "PAD_PAIR-4X10")
      (footprint "eagle-import:4X10_PAIR")
      (libsource (lib "eagle-import") (part "PAD_PAIR-4X10"))
    )
    (comp (ref "M4")
      (value "PAD_PAIR-4X10")
      (footprint "eagle-import:4X10_PAIR")
      (libsource (lib "eagle-import") (part "PAD_PAIR-4X10"))
    )
    (comp (ref "M5")
      (value "PAD_PAIR-4X10")
      (footprint "eagle-import:4X10_PAIR")
      (libsource (lib "eagle-import") (part "PAD_PAIR-4X10"))
    )
    (comp (ref "M6")
      (value "PAD_PAIR-4X10")
      (footprint "eagle-import:4X10_PAIR")
      (libsource (lib "eagle-import") (part "PAD_PAIR-4X10"))
    )
    (comp (ref "PAD1")
      (value "PAD-10X4")
      (footprint "eagle-import:10X4")
      (libsource (lib "eagle-import") (part "PAD-10X4"))
    )
    (comp (ref "PAD2")
      (value "PAD-10X4")
      (footprint "eagle-import:10X4")
      (libsource (lib "eagle-import") (part "PAD-10X4"))
    )
    (comp (ref "PAD3")
      (value "PAD-S_2X2")
      (footprint "eagle-import:2х2")
      (libsource (lib "eagle-import") (part "PAD-S_2X2"))
    )
    (comp (ref "PAD4")
      (value "PAD-S_2X2")
      (footprint "eagle-import:2х2")
      (libsource (lib "eagle-import") (part "PAD-S_2X2"))
    )
    (comp (ref "PAD5")
      (value "PAD-10X4")
      (footprint "eagle-import:10X4")
      (libsource (lib "eagle-import") (part "PAD-10X4"))
    )
    (comp (ref "PAD6")
      (value "PAD-10X4")
      (footprint "eagle-import:10X4")
      (libsource (lib "eagle-import") (part "PAD-10X4"))
    )
    (comp (ref "PAD7")
      (value "PAD-10X4")
      (footprint "eagle-import:10X4")
      (libsource (lib "eagle-import") (part "PAD-10X4"))
    )
    (comp (ref "PAD10")
      (value "PAD-10X4")
      (footprint "eagle-import:10X4")
      (libsource (lib "eagle-import") (part "PAD-10X4"))
    )
    (comp (ref "PAD25")
      (value "PAD-S_2X2")
      (footprint "eagle-import:2х2")
      (libsource (lib "eagle-import") (part "PAD-S_2X2"))
    )
    (comp (ref "PAD26")
      (value "PAD-S_2X2")
      (footprint "eagle-import:2х2")
      (libsource (lib "eagle-import") (part "PAD-S_2X2"))
    )
    (comp (ref "PAD27")
      (value "PAD-S_2X2")
      (footprint "eagle-import:2х2")
      (libsource (lib "eagle-import") (part "PAD-S_2X2"))
    )
    (comp (ref "PAD28")
      (value "PAD_PAIR-2X6")
      (footprint "eagle-import:2X6_PAIR")
      (libsource (lib "eagle-import") (part "PAD_PAIR-2X6"))
    )
    (comp (ref "PAD29")
      (value "PAD_PAIR-2X6")
      (footprint "eagle-import:2X6_PAIR")
      (libsource (lib "eagle-import") (part "PAD_PAIR-2X6"))
    )
    (comp (ref "PAD30")
      (value "PAD_PAIR-2X6")
      (footprint "eagle-import:2X6_PAIR")
      (libsource (lib "eagle-import") (part "PAD_PAIR-2X6"))
    )
    (comp (ref "PAD31")
      (value "PAD_PAIR-2X6")
      (footprint "eagle-import:2X6_PAIR")
      (libsource (lib "eagle-import") (part "PAD_PAIR-2X6"))
    )
    (comp (ref "PAD32")
      (value "PAD_PAIR-2X6")
      (footprint "eagle-import:2X6_PAIR")
      (libsource (lib "eagle-import") (part "PAD_PAIR-2X6"))
    )
    (comp (ref "PAD33")
      (value "PAD_PAIR-2X6")
      (footprint "eagle-import:2X6_PAIR")
      (libsource (lib "eagle-import") (part "PAD_PAIR-2X6"))
    )
    (comp (ref "R1")
      (value "120R")
      (footprint "eagle-import:R0603")
      (fields
        (field (name "PACKAGE") "0603")
        (field (name "TOLERANCE") "1%")
        (field (name "ALLOCATED") "+")
        (field (name "LCSC#") "C22787")
        (field (name "MANF") "UNI-ROYAL(Uniroyal Elec)")
        (field (name "MANF#") "0603WAF1200T5E")
      )
      (libsource (lib "eagle-import") (part "R-0603-1%"))
    )
    (comp (ref "R2")
      (value "120R")
      (footprint "eagle-import:R0603")
      (fields
        (field (name "PACKAGE") "0603")
        (field (name "TOLERANCE") "1%")
        (field (name "ALLOCATED") "+")
        (field (name "LCSC#") "C22787")
        (field (name "MANF") "UNI-ROYAL(Uniroyal Elec)")
        (field (name "MANF#") "0603WAF1200T5E")
      )
      (libsource (lib "eagle-import") (part "R-0603-1%"))
    )
    (comp (ref "R3")
      (value "82K")
      (footprint "eagle-import:R0603")
      (fields
        (field (name "PACKAGE") "0603")
        (field (name "TOLERANCE") "1%")
        (field (name "ALLOCATED") "+")
        (field (name "LCSC#") "C23254")
        (field (name "MANF") "UNI-ROYAL(Uniroyal Elec)")
        (field (name "MANF#") "0603WAF8202T5E")
      )
      (libsource (lib "eagle-import") (part "R-0603-1%"))
    )
    (comp (ref "R4")
      (value "200 µOhms")
      (footprint "eagle-import:R3920-KELVIN")
      (fields
        (field (name "MANF") "Bourns Inc")
        (field (name "POWER") "12W")
        (field (name "TOLERANCE") "±1%")
      )
      (libsource (lib "eagle-import") (part "CURRENT_SHUNT_KELVIN-3920-KELVIN-0.0002R"))
    )
    (comp (ref "R13")
      (value "10K2")
      (footprint "eagle-import:R0603")
      (fields
        (field (name "PACKAGE") "0603")
        (field (name "TOLERANCE") "1%")
        (field (name "ALLOCATED") "+")
        (field (name "LCSC#") "C22772")
        (field (name "MANF") "UNI-ROYAL(Uniroyal Elec)")
        (field (name "MANF#") "0603WAF1022T5E")
      )
      (libsource (lib "eagle-import") (part "R-0603-1%"))
    )
    (comp (ref "R14")
      (value "82K")
      (footprint "eagle-import:R0603")
      (fields
        (field (name "PACKAGE") "0603")
        (field (name "TOLERANCE") "1%")
        (field (name "ALLOCATED") "+")
        (field (name "LCSC#") "C23254")
        (field (name "MANF") "UNI-ROYAL(Uniroyal Elec)")
        (field (name "MANF#") "0603WAF8202T5E")
      )
      (libsource (lib "eagle-import") (part "R-0603-1%"))
    )
    (comp (ref "R15")
      (value "82K")
      (footprint "eagle-import:R0603")
      (fields
        (field (name "PACKAGE") "0603")
        (field (name "TOLERANCE") "1%")
        (field (name "ALLOCATED") "+")
        (field (name "LCSC#") "C23254")
        (field (name "MANF") "UNI-ROYAL(Uniroyal Elec)")
        (field (name "MANF#") "0603WAF8202T5E")
      )
      (libsource (lib "eagle-import") (part "R-0603-1%"))
    )
    (comp (ref "R18")
      (value "1K")
      (footprint "eagle-import:R0603")
      (fields
        (field (name "PACKAGE") "0603")
        (field (name "TOLERANCE") "1%")
        (field (name "ALLOCATED") "+")
        (field (name "LCSC#") "C21190")
        (field (name "MANF") "UNI-ROYAL(Uniroyal Elec)")
        (field (name "MANF#") "0603WAF1001T5E")
      )
      (libsource (lib "eagle-import") (part "R-0603-1%"))
    )
    (comp (ref "SJ2")
      (value "SOLDER_JOINT-SJ1")
      (footprint "eagle-import:RES_0")
      (libsource (lib "eagle-import") (part "SOLDER_JOINT-SJ1"))
    )
  )
  (nets
    (net (code "1") (name "ALARM") (class "Default")
      (node (ref "CON1") (pin "24") (pinfunction "24_24") (pintype "bidirectional"))
    )
    (net (code "2") (name "AUX_BATT_CURRENT_SENS") (class "Default")
      (node (ref "CON1") (pin "25") (pinfunction "25_25") (pintype "bidirectional"))
    )
    (net (code "3") (name "AUX_BATT_VOLTAGE_SENS") (class "Default")
      (node (ref "CON1") (pin "23") (pinfunction "23_23") (pintype "bidirectional"))
    )
    (net (code "4") (name "BAT1_MID") (class "Default")
      (node (ref "BAT1PAD2") (pin "1") (pinfunction "P$1_1") (pintype "bidirectional"))
      (node (ref "PAD7") (pin "P$1") (pinfunction "P$1_P$1") (pintype "bidirectional"))
    )
    (net (code "5") (name "BAT2_MID") (class "Default")
      (node (ref "BAT2PAD2") (pin "1") (pinfunction "P$1_1") (pintype "bidirectional"))
      (node (ref "PAD2") (pin "P$1") (pinfunction "P$1_P$1") (pintype "bidirectional"))
    )
    (net (code "6") (name "BAT3_MID") (class "Default")
      (node (ref "BAT3PAD2") (pin "1") (pinfunction "P$1_1") (pintype "bidirectional"))
      (node (ref "PAD6") (pin "P$1") (pinfunction "P$1_P$1") (pintype "bidirectional"))
    )
    (net (code "7") (name "BATT_CURRENT_SENS_PROT") (class "Default")
      (node (ref "C3") (pin "2") (pinfunction "2_2") (pintype "passive"))
      (node (ref "CON1") (pin "49") (pinfunction "49_49") (pintype "bidirectional"))
      (node (ref "IC1") (pin "1") (pinfunction "OUT_1") (pintype "bidirectional"))
      (node (ref "R3") (pin "2") (pinfunction "2_2") (pintype "passive"))
    )
    (net (code "8") (name "BATT_VOLTAGE_SENS_PROT") (class "Default")
      (node (ref "C4") (pin "2") (pinfunction "2_2") (pintype "passive"))
      (node (ref "CON1") (pin "47") (pinfunction "47_47") (pintype "bidirectional"))
      (node (ref "R13") (pin "2") (pinfunction "2_2") (pintype "passive"))
      (node (ref "R15") (pin "1") (pinfunction "1_1") (pintype "passive"))
    )
    (net (code "9") (name "CAN1_H") (class "Default")
      (node (ref "CON1") (pin "79") (pinfunction "79_79") (pintype "bidirectional"))
      (node (ref "CON20") (pin "2") (pinfunction "2_2") (pintype "bidirectional"))
      (node (ref "R2") (pin "1") (pinfunction "1_1") (pintype "passive"))
    )
    (net (code "10") (name "CAN1_L") (class "Default")
      (node (ref "CON1") (pin "77") (pinfunction "77_77") (pintype "bidirectional"))
      (node (ref "CON20") (pin "3") (pinfunction "3_3") (pintype "bidirectional"))
      (node (ref "SJ2") (pin "2") (pinfunction "2_2") (pintype "passive"))
    )
    (net (code "11") (name "CAN2_H") (class "Default")
      (node (ref "CON1") (pin "41") (pinfunction "41_41") (pintype "bidirectional"))
      (node (ref "CON10") (pin "2") (pinfunction "2_2") (pintype "bidirectional"))
      (node (ref "CON11") (pin "2") (pinfunction "2_2") (pintype "bidirectional"))
      (node (ref "CON12") (pin "2") (pinfunction "2_2") (pintype "bidirectional"))
      (node (ref "CON21") (pin "2") (pinfunction "2_2") (pintype "bidirectional"))
      (node (ref "CON6") (pin "2") (pinfunction "2_2") (pintype "bidirectional"))
      (node (ref "CON7") (pin "2") (pinfunction "2_2") (pintype "bidirectional"))
      (node (ref "CON8") (pin "2") (pinfunction "2_2") (pintype "bidirectional"))
      (node (ref "CON9") (pin "2") (pinfunction "2_2") (pintype "bidirectional"))
      (node (ref "R1") (pin "1") (pinfunction "1_1") (pintype "passive"))
    )
    (net (code "12") (name "CAN2_L") (class "Default")
      (node (ref "CON1") (pin "39") (pinfunction "39_39") (pintype "bidirectional"))
      (node (ref "CON10") (pin "3") (pinfunction "3_3") (pintype "bidirectional"))
      (node (ref "CON11") (pin "3") (pinfunction "3_3") (pintype "bidirectional"))
      (node (ref "CON12") (pin "3") (pinfunction "3_3") (pintype "bidirectional"))
      (node (ref "CON21") (pin "3") (pinfunction "3_3") (pintype "bidirectional"))
      (node (ref "CON6") (pin "3") (pinfunction "3_3") (pintype "bidirectional"))
      (node (ref "CON7") (pin "3") (pinfunction "3_3") (pintype "bidirectional"))
      (node (ref "CON8") (pin "3") (pinfunction "3_3") (pintype "bidirectional"))
      (node (ref "CON9") (pin "3") (pinfunction "3_3") (pintype "bidirectional"))
      (node (ref "R1") (pin "2") (pinfunction "2_2") (pintype "passive"))
    )
    (net (code "13") (name "CAN3_H") (class "Default")
      (node (ref "CON1") (pin "10") (pinfunction "10_10") (pintype "bidirectional"))
    )
    (net (code "14") (name "CAN3_L") (class "Default")
      (node (ref "CON1") (pin "8") (pinfunction "8_8") (pintype "bidirectional"))
    )
    (net (code "15") (name "ETH_RX+") (class "Default")
      (node (ref "CON18") (pin "2") (pinfunction "2_2") (pintype "passive"))
      (node (ref "CON5") (pin "2") (pinfunction "2_2") (pintype "bidirectional"))
    )
    (net (code "16") (name "ETH_RX-") (class "Default")
      (node (ref "CON18") (pin "1") (pinfunction "1_1") (pintype "passive"))
      (node (ref "CON5") (pin "1") (pinfunction "1_1") (pintype "bidirectional"))
    )
    (net (code "17") (name "ETH_TX+") (class "Default")
      (node (ref "CON18") (pin "4") (pinfunction "4_4") (pintype "passive"))
      (node (ref "CON5") (pin "4") (pinfunction "4_4") (pintype "bidirectional"))
    )
    (net (code "18") (name "ETH_TX-") (class "Default")
      (node (ref "CON18") (pin "3") (pinfunction "3_3") (pintype "passive"))
      (node (ref "CON5") (pin "3") (pinfunction "3_3") (pintype "bidirectional"))
    )
    (net (code "19") (name "EXTERN_DRDY") (class "Default")
      (node (ref "CON1") (pin "11") (pinfunction "11_11") (pintype "bidirectional"))
    )
    (net (code "20") (name "FMU-CH1-PROT{slash}MOTOR1") (class "Default")
      (node (ref "CON1") (pin "50") (pinfunction "50_50") (pintype "bidirectional"))
      (node (ref "PAD28") (pin "2") (pinfunction "P$1_2") (pintype "bidirectional"))
    )
    (net (code "21") (name "FMU-CH2-PROT{slash}MOTOR2") (class "Default")
      (node (ref "CON1") (pin "52") (pinfunction "52_52") (pintype "bidirectional"))
      (node (ref "PAD29") (pin "2") (pinfunction "P$1_2") (pintype "bidirectional"))
    )
    (net (code "22") (name "FMU-CH3-PROT{slash}MOTOR3") (class "Default")
      (node (ref "CON1") (pin "54") (pinfunction "54_54") (pintype "bidirectional"))
      (node (ref "PAD30") (pin "2") (pinfunction "P$1_2") (pintype "bidirectional"))
    )
    (net (code "23") (name "FMU-CH4-PROT{slash}MOTOR4") (class "Default")
      (node (ref "CON1") (pin "56") (pinfunction "56_56") (pintype "bidirectional"))
      (node (ref "PAD31") (pin "2") (pinfunction "P$1_2") (pintype "bidirectional"))
    )
    (net (code "24") (name "FMU-CH5-PROT{slash}MOTOR5") (class "Default")
      (node (ref "CON1") (pin "58") (pinfunction "58_58") (pintype "bidirectional"))
      (node (ref "PAD32") (pin "2") (pinfunction "P$1_2") (pintype "bidirectional"))
    )
    (net (code "25") (name "FMU-CH6-PROT{slash}MOTOR6") (class "Default")
      (node (ref "CON1") (pin "60") (pinfunction "60_60") (pintype "bidirectional"))
      (node (ref "PAD33") (pin "2") (pinfunction "P$1_2") (pintype "bidirectional"))
    )
    (net (code "26") (name "FMU-SWCLK") (class "Default")
      (node (ref "CON1") (pin "3") (pinfunction "3_3") (pintype "bidirectional"))
      (node (ref "PAD25") (pin "P$1") (pinfunction "P$1_P$1") (pintype "bidirectional"))
    )
    (net (code "27") (name "FMU-SWDIO") (class "Default")
      (node (ref "CON1") (pin "1") (pinfunction "1_1") (pintype "bidirectional"))
      (node (ref "PAD26") (pin "P$1") (pinfunction "P$1_P$1") (pintype "bidirectional"))
    )
    (net (code "28") (name "FMU-~{RESET}") (class "Default")
      (node (ref "CON1") (pin "7") (pinfunction "7_7") (pintype "bidirectional"))
      (node (ref "PAD27") (pin "P$1") (pinfunction "P$1_P$1") (pintype "bidirectional"))
    )
    (net (code "29") (name "GND") (class "Default")
      (node (ref "C1") (pin "1") (pinfunction "1_1") (pintype "passive"))
      (node (ref "C11") (pin "1") (pinfunction "1_1") (pintype "passive"))
      (node (ref "C12") (pin "1") (pinfunction "1_1") (pintype "passive"))
      (node (ref "C13") (pin "1") (pinfunction "1_1") (pintype "passive"))
      (node (ref "C14") (pin "1") (pinfunction "1_1") (pintype "passive"))
      (node (ref "C15") (pin "1") (pinfunction "1_1") (pintype "passive"))
      (node (ref "C16") (pin "P$1") (pinfunction "1_P$1") (pintype "passive"))
      (node (ref "C17") (pin "P$1") (pinfunction "1_P$1") (pintype "passive"))
      (node (ref "C18") (pin "P$1") (pinfunction "1_P$1") (pintype "passive"))
      (node (ref "C3") (pin "1") (pinfunction "1_1") (pintype "passive"))
      (node (ref "C38") (pin "1") (pinfunction "1_1") (pintype "passive"))
      (node (ref "C39") (pin "1") (pinfunction "1_1") (pintype "passive"))
      (node (ref "C4") (pin "1") (pinfunction "1_1") (pintype "passive"))
      (node (ref "C40") (pin "1") (pinfunction "1_1") (pintype "passive"))
      (node (ref "C41") (pin "1") (pinfunction "1_1") (pintype "passive"))
      (node (ref "C42") (pin "1") (pinfunction "1_1") (pintype "passive"))
      (node (ref "C43") (pin "1") (pinfunction "1_1") (pintype "passive"))
      (node (ref "C44") (pin "1") (pinfunction "1_1") (pintype "passive"))
      (node (ref "C45") (pin "1") (pinfunction "1_1") (pintype "passive"))
      (node (ref "C56") (pin "1") (pinfunction "1_1") (pintype "passive"))
      (node (ref "C57") (pin "1") (pinfunction "1_1") (pintype "passive"))
      (node (ref "C58") (pin "1") (pinfunction "1_1") (pintype "passive"))
      (node (ref "C59") (pin "1") (pinfunction "1_1") (pintype "passive"))
      (node (ref "C60") (pin "1") (pinfunction "1_1") (pintype "passive"))
      (node (ref "C61") (pin "1") (pinfunction "1_1") (pintype "passive"))
      (node (ref "C62") (pin "1") (pinfunction "1_1") (pintype "passive"))
      (node (ref "C63") (pin "1") (pinfunction "1_1") (pintype "passive"))
      (node (ref "CON1") (pin "13") (pinfunction "13_13") (pintype "bidirectional"))
      (node (ref "CON1") (pin "15") (pinfunction "15_15") (pintype "bidirectional"))
      (node (ref "CON1") (pin "55") (pinfunction "55_55") (pintype "bidirectional"))
      (node (ref "CON10") (pin "4") (pinfunction "4_4") (pintype "bidirectional"))
      (node (ref "CON10") (pin "M$0") (pinfunction "GND_M$0") (pintype "bidirectional"))
      (node (ref "CON10") (pin "M$1") (pinfunction "GND_M$1") (pintype "bidirectional"))
      (node (ref "CON11") (pin "4") (pinfunction "4_4") (pintype "bidirectional"))
      (node (ref "CON11") (pin "M$0") (pinfunction "GND_M$0") (pintype "bidirectional"))
      (node (ref "CON11") (pin "M$1") (pinfunction "GND_M$1") (pintype "bidirectional"))
      (node (ref "CON12") (pin "4") (pinfunction "4_4") (pintype "bidirectional"))
      (node (ref "CON12") (pin "M$0") (pinfunction "GND_M$0") (pintype "bidirectional"))
      (node (ref "CON12") (pin "M$1") (pinfunction "GND_M$1") (pintype "bidirectional"))
      (node (ref "CON13") (pin "1") (pinfunction "1_1") (pintype "bidirectional"))
      (node (ref "CON13") (pin "M$0") (pinfunction "GND_M$0") (pintype "bidirectional"))
      (node (ref "CON13") (pin "M$1") (pinfunction "GND_M$1") (pintype "bidirectional"))
      (node (ref "CON14") (pin "1") (pinfunction "1_1") (pintype "passive"))
      (node (ref "CON15") (pin "1") (pinfunction "1_1") (pintype "passive"))
      (node (ref "CON16") (pin "1") (pinfunction "1_1") (pintype "passive"))
      (node (ref "CON16") (pin "M$0") (pinfunction "G1_M$0") (pintype "passive"))
      (node (ref "CON16") (pin "M$1") (pinfunction "G1_M$1") (pintype "passive"))
      (node (ref "CON17") (pin "1") (pinfunction "1_1") (pintype "bidirectional"))
      (node (ref "CON17") (pin "M$0") (pinfunction "GND_M$0") (pintype "bidirectional"))
      (node (ref "CON17") (pin "M$1") (pinfunction "GND_M$1") (pintype "bidirectional"))
      (node (ref "CON18") (pin "12") (pinfunction "12_12") (pintype "passive"))
      (node (ref "CON18") (pin "13") (pinfunction "13_13") (pintype "passive"))
      (node (ref "CON18") (pin "14") (pinfunction "14_14") (pintype "passive"))
      (node (ref "CON18") (pin "M$0") (pinfunction "G1_M$0") (pintype "passive"))
      (node (ref "CON18") (pin "M$1") (pinfunction "G1_M$1") (pintype "passive"))
      (node (ref "CON19") (pin "A1") (pinfunction "GND_A1") (pintype "bidirectional"))
      (node (ref "CON19") (pin "A12") (pinfunction "GND_A12") (pintype "bidirectional"))
      (node (ref "CON19") (pin "B1") (pinfunction "GND_B1") (pintype "bidirectional"))
      (node (ref "CON19") (pin "B12") (pinfunction "GND_B12") (pintype "bidirectional"))
      (node (ref "CON19") (pin "G1") (pinfunction "GND_G1") (pintype "bidirectional"))
      (node (ref "CON19") (pin "G10") (pinfunction "GND_G10") (pintype "bidirectional"))
      (node (ref "CON19") (pin "G2") (pinfunction "GND_G2") (pintype "bidirectional"))
      (node (ref "CON19") (pin "G4") (pinfunction "GND_G4") (pintype "bidirectional"))
      (node (ref "CON19") (pin "G5") (pinfunction "GND_G5") (pintype "bidirectional"))
      (node (ref "CON19") (pin "G7") (pinfunction "GND_G7") (pintype "bidirectional"))
      (node (ref "CON19") (pin "G8") (pinfunction "GND_G8") (pintype "bidirectional"))
      (node (ref "CON19") (pin "G9") (pinfunction "GND_G9") (pintype "bidirectional"))
      (node (ref "CON19") (pin "P$1") (pinfunction "GND_P$1") (pintype "bidirectional"))
      (node (ref "CON19") (pin "P$2") (pinfunction "GND_P$2") (pintype "bidirectional"))
      (node (ref "CON2") (pin "1") (pinfunction "1_1") (pintype "bidirectional"))
      (node (ref "CON2") (pin "M$0") (pinfunction "GND_M$0") (pintype "bidirectional"))
      (node (ref "CON2") (pin "M$1") (pinfunction "GND_M$1") (pintype "bidirectional"))
      (node (ref "CON20") (pin "4") (pinfunction "4_4") (pintype "bidirectional"))
      (node (ref "CON20") (pin "M$0") (pinfunction "GND_M$0") (pintype "bidirectional"))
      (node (ref "CON20") (pin "M$1") (pinfunction "GND_M$1") (pintype "bidirectional"))
      (node (ref "CON21") (pin "4") (pinfunction "4_4") (pintype "bidirectional"))
      (node (ref "CON21") (pin "M$0") (pinfunction "GND_M$0") (pintype "bidirectional"))
      (node (ref "CON21") (pin "M$1") (pinfunction "GND_M$1") (pintype "bidirectional"))
      (node (ref "CON3") (pin "1") (pinfunction "1_1") (pintype "bidirectional"))
      (node (ref "CON3") (pin "4") (pinfunction "4_4") (pintype "bidirectional"))
      (node (ref "CON3") (pin "M$0") (pinfunction "GND_M$0") (pintype "bidirectional"))
      (node (ref "CON3") (pin "M$1") (pinfunction "GND_M$1") (pintype "bidirectional"))
      (node (ref "CON4") (pin "1") (pinfunction "1_1") (pintype "bidirectional"))
      (node (ref "CON4") (pin "M$0") (pinfunction "GND_M$0") (pintype "bidirectional"))
      (node (ref "CON4") (pin "M$1") (pinfunction "GND_M$1") (pintype "bidirectional"))
      (node (ref "CON5") (pin "M$0") (pinfunction "GND_M$0") (pintype "bidirectional"))
      (node (ref "CON5") (pin "M$1") (pinfunction "GND_M$1") (pintype "bidirectional"))
      (node (ref "CON6") (pin "4") (pinfunction "4_4") (pintype "bidirectional"))
      (node (ref "CON6") (pin "M$0") (pinfunction "GND_M$0") (pintype "bidirectional"))
      (node (ref "CON6") (pin "M$1") (pinfunction "GND_M$1") (pintype "bidirectional"))
      (node (ref "CON7") (pin "4") (pinfunction "4_4") (pintype "bidirectional"))
      (node (ref "CON7") (pin "M$0") (pinfunction "GND_M$0") (pintype "bidirectional"))
      (node (ref "CON7") (pin "M$1") (pinfunction "GND_M$1") (pintype "bidirectional"))
      (node (ref "CON8") (pin "4") (pinfunction "4_4") (pintype "bidirectional"))
      (node (ref "CON8") (pin "M$0") (pinfunction "GND_M$0") (pintype "bidirectional"))
      (node (ref "CON8") (pin "M$1") (pinfunction "GND_M$1") (pintype "bidirectional"))
      (node (ref "CON9") (pin "4") (pinfunction "4_4") (pintype "bidirectional"))
      (node (ref "CON9") (pin "M$0") (pinfunction "GND_M$0") (pintype "bidirectional"))
      (node (ref "CON9") (pin "M$1") (pinfunction "GND_M$1") (pintype "bidirectional"))
      (node (ref "D2") (pin "A") (pinfunction "A_A") (pintype "passive"))
      (node (ref "D5") (pin "A") (pinfunction "A_A") (pintype "passive"))
      (node (ref "D7") (pin "A") (pinfunction "A_A") (pintype "passive"))
      (node (ref "IC1") (pin "2") (pinfunction "GND_2") (pintype "bidirectional"))
      (node (ref "IC2") (pin "7") (pinfunction "GND_7") (pintype "bidirectional"))
      (node (ref "IC2") (pin "P$1") (pinfunction "GND_P$1") (pintype "bidirectional"))
      (node (ref "IC5") (pin "7") (pinfunction "GND_7") (pintype "bidirectional"))
      (node (ref "IC5") (pin "P$1") (pinfunction "GND_P$1") (pintype "bidirectional"))
      (node (ref "IC7") (pin "7") (pinfunction "GND_7") (pintype "bidirectional"))
      (node (ref "IC7") (pin "P$1") (pinfunction "GND_P$1") (pintype "bidirectional"))
      (node (ref "J1") (pin "1") (pinfunction "P$1_1") (pintype "bidirectional"))
      (node (ref "LED1") (pin "C") (pinfunction "C_C") (pintype "bidirectional"))
      (node (ref "LED2") (pin "C") (pinfunction "C_C") (pintype "bidirectional"))
      (node (ref "LED3") (pin "C") (pinfunction "C_C") (pintype "bidirectional"))
      (node (ref "PAD13") (pin "P$1") (pinfunction "P$1_P$1") (pintype "bidirectional"))
      (node (ref "PAD16") (pin "P$1") (pinfunction "P$1_P$1") (pintype "bidirectional"))
      (node (ref "PAD18") (pin "P$1") (pinfunction "P$1_P$1") (pintype "bidirectional"))
      (node (ref "PAD28") (pin "1") (pinfunction "P$1_1") (pintype "bidirectional"))
      (node (ref "PAD29") (pin "1") (pinfunction "P$1_1") (pintype "bidirectional"))
      (node (ref "PAD30") (pin "1") (pinfunction "P$1_1") (pintype "bidirectional"))
      (node (ref "PAD31") (pin "1") (pinfunction "P$1_1") (pintype "bidirectional"))
      (node (ref "PAD32") (pin "1") (pinfunction "P$1_1") (pintype "bidirectional"))
      (node (ref "PAD33") (pin "1") (pinfunction "P$1_1") (pintype "bidirectional"))
      (node (ref "PAD4") (pin "P$1") (pinfunction "P$1_P$1") (pintype "bidirectional"))
      (node (ref "R12") (pin "1") (pinfunction "1_1") (pintype "passive"))
      (node (ref "R13") (pin "1") (pinfunction "1_1") (pintype "passive"))
      (node (ref "R17") (pin "1") (pinfunction "1_1") (pintype "passive"))
      (node (ref "R27") (pin "1") (pinfunction "1_1") (pintype "passive"))
      (node (ref "R3") (pin "1") (pinfunction "1_1") (pintype "passive"))
      (node (ref "R30") (pin "1") (pinfunction "1_1") (pintype "passive"))
      (node (ref "R39") (pin "1") (pinfunction "1_1") (pintype "passive"))
      (node (ref "R42") (pin "1") (pinfunction "1_1") (pintype "passive"))
      (node (ref "R9") (pin "1") (pinfunction "1_1") (pintype "passive"))
    )
    (net (code "30") (name "I2C1_SCL") (class "Default")
      (node (ref "CON1") (pin "37") (pinfunction "37_37") (pintype "bidirectional"))
    )
    (net (code "31") (name "I2C1_SDA") (class "Default")
      (node (ref "CON1") (pin "35") (pinfunction "35_35") (pintype "bidirectional"))
    )
    (net (code "32") (name "IO-CH1-PROT") (class "Default")
      (node (ref "CON1") (pin "80") (pinfunction "80_80") (pintype "bidirectional"))
      (node (ref "CON16") (pin "2") (pinfunction "2_2") (pintype "passive"))
    )
    (net (code "33") (name "IO-CH2-PROT") (class "Default")
      (node (ref "CON1") (pin "78") (pinfunction "78_78") (pintype "bidirectional"))
      (node (ref "CON16") (pin "3") (pinfunction "3_3") (pintype "passive"))
    )
    (net (code "34") (name "IO-CH3-PROT") (class "Default")
      (node (ref "CON1") (pin "76") (pinfunction "76_76") (pintype "bidirectional"))
      (node (ref "CON16") (pin "4") (pinfunction "4_4") (pintype "passive"))
    )
    (net (code "35") (name "IO-CH4-PROT") (class "Default")
      (node (ref "CON1") (pin "74") (pinfunction "74_74") (pintype "bidirectional"))
      (node (ref "CON16") (pin "5") (pinfunction "5_5") (pintype "passive"))
    )
    (net (code "36") (name "IO-CH5-PROT") (class "Default")
      (node (ref "CON1") (pin "72") (pinfunction "72_72") (pintype "bidirectional"))
      (node (ref "CON16") (pin "6") (pinfunction "6_6") (pintype "passive"))
    )
    (net (code "37") (name "IO-CH6-PROT") (class "Default")
      (node (ref "CON1") (pin "70") (pinfunction "70_70") (pintype "bidirectional"))
    )
    (net (code "38") (name "IO-CH7-PROT{slash}24V_EN") (class "Default")
      (node (ref "CON1") (pin "68") (pinfunction "68_68") (pintype "bidirectional"))
      (node (ref "R6") (pin "1") (pinfunction "1_1") (pintype "passive"))
    )
    (net (code "39") (name "IO-CH8-PROT{slash}12V_EN") (class "Default")
      (node (ref "CON1") (pin "66") (pinfunction "66_66") (pintype "bidirectional"))
      (node (ref "R5") (pin "1") (pinfunction "1_1") (pintype "passive"))
    )
    (net (code "40") (name "IO-SWCLK") (class "Default")
      (node (ref "CON1") (pin "71") (pinfunction "71_71") (pintype "bidirectional"))
    )
    (net (code "41") (name "IO-SWDIO") (class "Default")
      (node (ref "CON1") (pin "69") (pinfunction "69_69") (pintype "bidirectional"))
    )
    (net (code "42") (name "IO-~{RESET}") (class "Default")
      (node (ref "CON1") (pin "75") (pinfunction "75_75") (pintype "bidirectional"))
    )
    (net (code "43") (name "IO_USART1_RX_SPECTRUM_DSM") (class "Default")
      (node (ref "CON1") (pin "48") (pinfunction "48_48") (pintype "bidirectional"))
    )
    (net (code "44") (name "IO_USART1_TX") (class "Default")
      (node (ref "CON1") (pin "46") (pinfunction "46_46") (pintype "bidirectional"))
    )
    (net (code "45") (name "IO_VDD_3V3") (class "Default")
      (node (ref "CON1") (pin "26") (pinfunction "26_26") (pintype "bidirectional"))
    )
    (net (code "46") (name "IO_VDD_5V5") (class "Default")
      (node (ref "CON1") (pin "65") (pinfunction "65_65") (pintype "bidirectional"))
    )
    (net (code "47") (name "Net-(BAT1PAD1B-P$1)") (class "Default")
      (node (ref "BAT1PAD1") (pin "2") (pinfunction "P$1_2") (pintype "bidirectional"))
      (node (ref "PAD1") (pin "P$1") (pinfunction "P$1_P$1") (pintype "bidirectional"))
    )
    (net (code "48") (name "Net-(BAT2PAD1B-P$1)") (class "Default")
      (node (ref "BAT2PAD1") (pin "2") (pinfunction "P$1_2") (pintype "bidirectional"))
      (node (ref "PAD5") (pin "P$1") (pinfunction "P$1_P$1") (pintype "bidirectional"))
    )
    (net (code "49") (name "Net-(BAT3PAD1B-P$1)") (class "Default")
      (node (ref "BAT3PAD1") (pin "2") (pinfunction "P$1_2") (pintype "bidirectional"))
      (node (ref "PAD10") (pin "P$1") (pinfunction "P$1_P$1") (pintype "bidirectional"))
    )
    (net (code "50") (name "Net-(C14-Pad2)") (class "Default")
      (node (ref "C14") (pin "2") (pinfunction "2_2") (pintype "passive"))
      (node (ref "R10") (pin "1") (pinfunction "1_1") (pintype "passive"))
    )
    (net (code "51") (name "Net-(C41-Pad2)") (class "Default")
      (node (ref "C41") (pin "2") (pinfunction "2_2") (pintype "passive"))
      (node (ref "R28") (pin "1") (pinfunction "1_1") (pintype "passive"))
    )
    (net (code "52") (name "Net-(C43-Pad2)") (class "Default")
      (node (ref "C43") (pin "2") (pinfunction "2_2") (pintype "passive"))
      (node (ref "C44") (pin "2") (pinfunction "2_2") (pintype "passive"))
      (node (ref "C45") (pin "2") (pinfunction "2_2") (pintype "passive"))
      (node (ref "L5") (pin "2") (pinfunction "2_2") (pintype "bidirectional"))
      (node (ref "PAD14") (pin "P$1") (pinfunction "P$1_P$1") (pintype "bidirectional"))
      (node (ref "R29") (pin "2") (pinfunction "2_2") (pintype "passive"))
      (node (ref "SJ1") (pin "1") (pinfunction "1_1") (pintype "passive"))
    )
    (net (code "53") (name "Net-(C59-Pad2)") (class "Default")
      (node (ref "C59") (pin "2") (pinfunction "2_2") (pintype "passive"))
      (node (ref "R40") (pin "1") (pinfunction "1_1") (pintype "passive"))
    )
    (net (code "54") (name "Net-(CON1-Pad2)") (class "Default")
      (node (ref "CON1") (pin "2") (pinfunction "2_2") (pintype "bidirectional"))
      (node (ref "LED4") (pin "C") (pinfunction "C_C") (pintype "bidirectional"))
    )
    (net (code "55") (name "Net-(CON1-Pad4)") (class "Default")
      (node (ref "CON1") (pin "4") (pinfunction "4_4") (pintype "bidirectional"))
      (node (ref "CON15") (pin "4") (pinfunction "4_4") (pintype "passive"))
    )
    (net (code "56") (name "Net-(CON1-Pad6)") (class "Default")
      (node (ref "CON1") (pin "6") (pinfunction "6_6") (pintype "bidirectional"))
      (node (ref "CON15") (pin "3") (pinfunction "3_3") (pintype "passive"))
    )
    (net (code "57") (name "Net-(IC1-VIN+)") (class "Default")
      (node (ref "IC1") (pin "3") (pinfunction "VIN+_3") (pintype "bidirectional"))
      (node (ref "R4") (pin "S1") (pinfunction "S1_S1") (pintype "bidirectional"))
    )
    (net (code "58") (name "Net-(IC1-VIN-)") (class "Default")
      (node (ref "IC1") (pin "4") (pinfunction "VIN-_4") (pintype "bidirectional"))
      (node (ref "R4") (pin "S2") (pinfunction "S2_S2") (pintype "bidirectional"))
    )
    (net (code "59") (name "Net-(IC2-BOOT)") (class "Default")
      (node (ref "C2") (pin "1") (pinfunction "1_1") (pintype "passive"))
      (node (ref "IC2") (pin "1") (pinfunction "BOOT_1") (pintype "bidirectional"))
    )
    (net (code "60") (name "Net-(IC2-COMP)") (class "Default")
      (node (ref "C15") (pin "2") (pinfunction "2_2") (pintype "passive"))
      (node (ref "IC2") (pin "6") (pinfunction "COMP_6") (pintype "bidirectional"))
      (node (ref "R10") (pin "2") (pinfunction "2_2") (pintype "passive"))
    )
    (net (code "61") (name "Net-(IC2-EN)") (class "Default")
      (node (ref "IC2") (pin "3") (pinfunction "EN_3") (pintype "bidirectional"))
      (node (ref "R6") (pin "2") (pinfunction "2_2") (pintype "passive"))
    )
    (net (code "62") (name "Net-(IC2-FB)") (class "Default")
      (node (ref "IC2") (pin "5") (pinfunction "FB_5") (pintype "bidirectional"))
      (node (ref "R11") (pin "1") (pinfunction "1_1") (pintype "passive"))
      (node (ref "R12") (pin "2") (pinfunction "2_2") (pintype "passive"))
      (node (ref "R17") (pin "2") (pinfunction "2_2") (pintype "passive"))
    )
    (net (code "63") (name "Net-(IC2-RT{slash}CLK)") (class "Default")
      (node (ref "IC2") (pin "4") (pinfunction "RT/CLK_4") (pintype "bidirectional"))
      (node (ref "R9") (pin "2") (pinfunction "2_2") (pintype "passive"))
    )
    (net (code "64") (name "Net-(IC2-SW)") (class "Default")
      (node (ref "C2") (pin "2") (pinfunction "2_2") (pintype "passive"))
      (node (ref "D2") (pin "C") (pinfunction "C_C") (pintype "passive"))
      (node (ref "IC2") (pin "8") (pinfunction "SW_8") (pintype "bidirectional"))
      (node (ref "L4") (pin "1") (pinfunction "1_1") (pintype "bidirectional"))
    )
    (net (code "65") (name "Net-(IC5-BOOT)") (class "Default")
      (node (ref "C37") (pin "1") (pinfunction "1_1") (pintype "passive"))
      (node (ref "IC5") (pin "1") (pinfunction "BOOT_1") (pintype "bidirectional"))
    )
    (net (code "66") (name "Net-(IC5-COMP)") (class "Default")
      (node (ref "C42") (pin "2") (pinfunction "2_2") (pintype "passive"))
      (node (ref "IC5") (pin "6") (pinfunction "COMP_6") (pintype "bidirectional"))
      (node (ref "R28") (pin "2") (pinfunction "2_2") (pintype "passive"))
    )
    (net (code "67") (name "Net-(IC5-FB)") (class "Default")
      (node (ref "IC5") (pin "5") (pinfunction "FB_5") (pintype "bidirectional"))
      (node (ref "R29") (pin "1") (pinfunction "1_1") (pintype "passive"))
      (node (ref "R30") (pin "2") (pinfunction "2_2") (pintype "passive"))
    )
    (net (code "68") (name "Net-(IC5-RT{slash}CLK)") (class "Default")
      (node (ref "IC5") (pin "4") (pinfunction "RT/CLK_4") (pintype "bidirectional"))
      (node (ref "R27") (pin "2") (pinfunction "2_2") (pintype "passive"))
    )
    (net (code "69") (name "Net-(IC5-SW)") (class "Default")
      (node (ref "C37") (pin "2") (pinfunction "2_2") (pintype "passive"))
      (node (ref "D5") (pin "C") (pinfunction "C_C") (pintype "passive"))
      (node (ref "IC5") (pin "8") (pinfunction "SW_8") (pintype "bidirectional"))
      (node (ref "L5") (pin "1") (pinfunction "1_1") (pintype "bidirectional"))
    )
    (net (code "70") (name "Net-(IC7-BOOT)") (class "Default")
      (node (ref "C55") (pin "1") (pinfunction "1_1") (pintype "passive"))
      (node (ref "IC7") (pin "1") (pinfunction "BOOT_1") (pintype "bidirectional"))
    )
    (net (code "71") (name "Net-(IC7-COMP)") (class "Default")
      (node (ref "C60") (pin "2") (pinfunction "2_2") (pintype "passive"))
      (node (ref "IC7") (pin "6") (pinfunction "COMP_6") (pintype "bidirectional"))
      (node (ref "R40") (pin "2") (pinfunction "2_2") (pintype "passive"))
    )
    (net (code "72") (name "Net-(IC7-EN)") (class "Default")
      (node (ref "IC7") (pin "3") (pinfunction "EN_3") (pintype "bidirectional"))
      (node (ref "R5") (pin "2") (pinfunction "2_2") (pintype "passive"))
    )
    (net (code "73") (name "Net-(IC7-FB)") (class "Default")
      (node (ref "IC7") (pin "5") (pinfunction "FB_5") (pintype "bidirectional"))
      (node (ref "R41") (pin "1") (pinfunction "1_1") (pintype "passive"))
      (node (ref "R42") (pin "2") (pinfunction "2_2") (pintype "passive"))
    )
    (net (code "74") (name "Net-(IC7-RT{slash}CLK)") (class "Default")
      (node (ref "IC7") (pin "4") (pinfunction "RT/CLK_4") (pintype "bidirectional"))
      (node (ref "R39") (pin "2") (pinfunction "2_2") (pintype "passive"))
    )
    (net (code "75") (name "Net-(IC7-SW)") (class "Default")
      (node (ref "C55") (pin "2") (pinfunction "2_2") (pintype "passive"))
      (node (ref "D7") (pin "C") (pinfunction "C_C") (pintype "passive"))
      (node (ref "IC7") (pin "8") (pinfunction "SW_8") (pintype "bidirectional"))
      (node (ref "L7") (pin "1") (pinfunction "1_1") (pintype "bidirectional"))
    )
    (net (code "76") (name "Net-(LED1-PadA)") (class "Default")
      (node (ref "LED1") (pin "A") (pinfunction "A_A") (pintype "bidirectional"))
      (node (ref "R7") (pin "2") (pinfunction "2_2") (pintype "passive"))
    )
    (net (code "77") (name "Net-(LED2-PadA)") (class "Default")
      (node (ref "LED2") (pin "A") (pinfunction "A_A") (pintype "bidirectional"))
      (node (ref "R8") (pin "2") (pinfunction "2_2") (pintype "passive"))
    )
    (net (code "78") (name "Net-(LED3-PadA)") (class "Default")
      (node (ref "LED3") (pin "A") (pinfunction "A_A") (pintype "bidirectional"))
      (node (ref "R16") (pin "2") (pinfunction "2_2") (pintype "passive"))
    )
    (net (code "79") (name "Net-(LED4-PadA)") (class "Default")
      (node (ref "LED4") (pin "A") (pinfunction "A_A") (pintype "bidirectional"))
      (node (ref "R18") (pin "2") (pinfunction "2_2") (pintype "passive"))
    )
    (net (code "80") (name "Net-(R2-Pad2)") (class "Default")
      (node (ref "R2") (pin "2") (pinfunction "2_2") (pintype "passive"))
      (node (ref "SJ2") (pin "1") (pinfunction "1_1") (pintype "passive"))
    )
    (net (code "81") (name "Net-(R14-Pad1)") (class "Default")
      (node (ref "R14") (pin "1") (pinfunction "1_1") (pintype "passive"))
      (node (ref "R15") (pin "2") (pinfunction "2_2") (pintype "passive"))
    )
    (net (code "82") (name "OTG_DM1") (class "Default")
      (node (ref "CON1") (pin "33") (pinfunction "33_33") (pintype "bidirectional"))
      (node (ref "CON14") (pin "4") (pinfunction "4_4") (pintype "passive"))
      (node (ref "CON19") (pin "A7") (pinfunction "D-_A7") (pintype "bidirectional"))
      (node (ref "CON19") (pin "B7") (pinfunction "D-_B7") (pintype "bidirectional"))
    )
    (net (code "83") (name "OTG_DP1") (class "Default")
      (node (ref "CON1") (pin "31") (pinfunction "31_31") (pintype "bidirectional"))
      (node (ref "CON14") (pin "3") (pinfunction "3_3") (pintype "passive"))
      (node (ref "CON19") (pin "A6") (pinfunction "D+_A6") (pintype "bidirectional"))
      (node (ref "CON19") (pin "B6") (pinfunction "D+_B6") (pintype "bidirectional"))
    )
    (net (code "84") (name "PGND") (class "Default")
      (node (ref "BAT1PAD2") (pin "2") (pinfunction "P$1_2") (pintype "bidirectional"))
      (node (ref "BAT2PAD2") (pin "2") (pinfunction "P$1_2") (pintype "bidirectional"))
      (node (ref "BAT3PAD2") (pin "2") (pinfunction "P$1_2") (pintype "bidirectional"))
      (node (ref "J1") (pin "2") (pinfunction "P$2_2") (pintype "bidirectional"))
      (node (ref "M1") (pin "2") (pinfunction "P$1_2") (pintype "bidirectional"))
      (node (ref "M2") (pin "2") (pinfunction "P$1_2") (pintype "bidirectional"))
      (node (ref "M3") (pin "2") (pinfunction "P$1_2") (pintype "bidirectional"))
      (node (ref "M4") (pin "2") (pinfunction "P$1_2") (pintype "bidirectional"))
      (node (ref "M5") (pin "2") (pinfunction "P$1_2") (pintype "bidirectional"))
      (node (ref "M6") (pin "2") (pinfunction "P$1_2") (pintype "bidirectional"))
    )
    (net (code "85") (name "PPM-SBUS-PROT") (class "Default")
      (node (ref "CON1") (pin "62") (pinfunction "62_62") (pintype "bidirectional"))
      (node (ref "CON2") (pin "3") (pinfunction "3_3") (pintype "bidirectional"))
    )
    (net (code "86") (name "PRESSURE_SENS_IN") (class "Default")
      (node (ref "CON1") (pin "21") (pinfunction "21_21") (pintype "bidirectional"))
    )
    (net (code "87") (name "S.BUS_OUT") (class "Default")
      (node (ref "CON1") (pin "64") (pinfunction "64_64") (pintype "bidirectional"))
    )
    (net (code "88") (name "SAFETY") (class "Default")
      (node (ref "CON1") (pin "17") (pinfunction "17_17") (pintype "bidirectional"))
    )
    (net (code "89") (name "SERIAL1_CTS") (class "Default")
      (node (ref "CON1") (pin "44") (pinfunction "44_44") (pintype "bidirectional"))
    )
    (net (code "90") (name "SERIAL1_RTS") (class "Default")
      (node (ref "CON1") (pin "42") (pinfunction "42_42") (pintype "bidirectional"))
    )
    (net (code "91") (name "SERIAL1_RX") (class "Default")
      (node (ref "CON1") (pin "38") (pinfunction "38_38") (pintype "bidirectional"))
      (node (ref "CON18") (pin "6") (pinfunction "6_6") (pintype "passive"))
    )
    (net (code "92") (name "SERIAL1_TX") (class "Default")
      (node (ref "CON1") (pin "40") (pinfunction "40_40") (pintype "bidirectional"))
      (node (ref "CON18") (pin "5") (pinfunction "5_5") (pintype "passive"))
    )
    (net (code "93") (name "SERIAL2_CTS") (class "Default")
      (node (ref "CON1") (pin "32") (pinfunction "32_32") (pintype "bidirectional"))
    )
    (net (code "94") (name "SERIAL2_RTS") (class "Default")
      (node (ref "CON1") (pin "30") (pinfunction "30_30") (pintype "bidirectional"))
    )
    (net (code "95") (name "SERIAL2_RX") (class "Default")
      (node (ref "CON1") (pin "34") (pinfunction "34_34") (pintype "bidirectional"))
      (node (ref "CON18") (pin "8") (pinfunction "8_8") (pintype "passive"))
    )
    (net (code "96") (name "SERIAL2_TX") (class "Default")
      (node (ref "CON1") (pin "36") (pinfunction "36_36") (pintype "bidirectional"))
      (node (ref "CON18") (pin "7") (pinfunction "7_7") (pintype "passive"))
    )
    (net (code "97") (name "SERIAL3_RX") (class "Default")
      (node (ref "CON1") (pin "20") (pinfunction "20_20") (pintype "bidirectional"))
      (node (ref "CON4") (pin "4") (pinfunction "4_4") (pintype "bidirectional"))
    )
    (net (code "98") (name "SERIAL3_TX") (class "Default")
      (node (ref "CON1") (pin "22") (pinfunction "22_22") (pintype "bidirectional"))
      (node (ref "CON4") (pin "3") (pinfunction "3_3") (pintype "bidirectional"))
    )
    (net (code "99") (name "SERIAL4_RX") (class "Default")
      (node (ref "CON1") (pin "16") (pinfunction "16_16") (pintype "bidirectional"))
      (node (ref "CON13") (pin "4") (pinfunction "4_4") (pintype "bidirectional"))
    )
    (net (code "100") (name "SERIAL4_TX") (class "Default")
      (node (ref "CON1") (pin "18") (pinfunction "18_18") (pintype "bidirectional"))
      (node (ref "CON13") (pin "3") (pinfunction "3_3") (pintype "bidirectional"))
    )
    (net (code "101") (name "SERIAL5_RX") (class "Default")
      (node (ref "CON1") (pin "12") (pinfunction "12_12") (pintype "bidirectional"))
      (node (ref "CON17") (pin "4") (pinfunction "4_4") (pintype "bidirectional"))
    )
    (net (code "102") (name "SERIAL5_TX") (class "Default")
      (node (ref "CON1") (pin "14") (pinfunction "14_14") (pintype "bidirectional"))
      (node (ref "CON17") (pin "3") (pinfunction "3_3") (pintype "bidirectional"))
    )
    (net (code "103") (name "SPI_EXT_MISO") (class "Default")
      (node (ref "CON1") (pin "67") (pinfunction "67_67") (pintype "bidirectional"))
    )
    (net (code "104") (name "SPI_EXT_MOSI") (class "Default")
      (node (ref "CON1") (pin "51") (pinfunction "51_51") (pintype "bidirectional"))
    )
    (net (code "105") (name "SPI_EXT_SCK") (class "Default")
      (node (ref "CON1") (pin "73") (pinfunction "73_73") (pintype "bidirectional"))
    )
    (net (code "106") (name "VBAT") (class "Default")
      (node (ref "BAT1PAD1") (pin "1") (pinfunction "P$1_1") (pintype "bidirectional"))
      (node (ref "BAT2PAD1") (pin "1") (pinfunction "P$1_1") (pintype "bidirectional"))
      (node (ref "BAT3PAD1") (pin "1") (pinfunction "P$1_1") (pintype "bidirectional"))
      (node (ref "R14") (pin "2") (pinfunction "2_2") (pintype "passive"))
      (node (ref "R4") (pin "1") (pinfunction "1_1") (pintype "bidirectional"))
      (node (ref "R4") (pin "11") (pinfunction "1_11") (pintype "bidirectional"))
    )
    (net (code "107") (name "VBUS") (class "Default")
      (node (ref "CON1") (pin "29") (pinfunction "29_29") (pintype "bidirectional"))
      (node (ref "CON14") (pin "2") (pinfunction "2_2") (pintype "passive"))
      (node (ref "CON19") (pin "A4") (pinfunction "VBUS_A4") (pintype "bidirectional"))
      (node (ref "CON19") (pin "B4") (pinfunction "VBUS_B4") (pintype "bidirectional"))
      (node (ref "D1") (pin "A") (pinfunction "A_A") (pintype "passive"))
    )
    (net (code "108") (name "VDC") (class "Default")
      (node (ref "C11") (pin "2") (pinfunction "2_2") (pintype "passive"))
      (node (ref "C12") (pin "2") (pinfunction "2_2") (pintype "passive"))
      (node (ref "C13") (pin "2") (pinfunction "2_2") (pintype "passive"))
      (node (ref "C38") (pin "2") (pinfunction "2_2") (pintype "passive"))
      (node (ref "C39") (pin "2") (pinfunction "2_2") (pintype "passive"))
      (node (ref "C40") (pin "2") (pinfunction "2_2") (pintype "passive"))
      (node (ref "C56") (pin "2") (pinfunction "2_2") (pintype "passive"))
      (node (ref "C57") (pin "2") (pinfunction "2_2") (pintype "passive"))
      (node (ref "C58") (pin "2") (pinfunction "2_2") (pintype "passive"))
      (node (ref "IC2") (pin "2") (pinfunction "VIN_2") (pintype "bidirectional"))
      (node (ref "IC5") (pin "2") (pinfunction "VIN_2") (pintype "bidirectional"))
      (node (ref "IC7") (pin "2") (pinfunction "VIN_2") (pintype "bidirectional"))
      (node (ref "M1") (pin "1") (pinfunction "P$1_1") (pintype "bidirectional"))
      (node (ref "M2") (pin "1") (pinfunction "P$1_1") (pintype "bidirectional"))
      (node (ref "M3") (pin "1") (pinfunction "P$1_1") (pintype "bidirectional"))
      (node (ref "M4") (pin "1") (pinfunction "P$1_1") (pintype "bidirectional"))
      (node (ref "M5") (pin "1") (pinfunction "P$1_1") (pintype "bidirectional"))
      (node (ref "M6") (pin "1") (pinfunction "P$1_1") (pintype "bidirectional"))
      (node (ref "R4") (pin "2") (pinfunction "2_2") (pintype "bidirectional"))
      (node (ref "R4") (pin "22") (pinfunction "2_22") (pintype "bidirectional"))
    )
    (net (code "109") (name "VDD_3V3_SPEKTRUM_EN") (class "Default")
      (node (ref "CON1") (pin "19") (pinfunction "19_19") (pintype "bidirectional"))
    )
    (net (code "110") (name "VDD_5V") (class "Default")
      (node (ref "C1") (pin "2") (pinfunction "2_2") (pintype "passive"))
      (node (ref "CON1") (pin "61") (pinfunction "61_61") (pintype "bidirectional"))
      (node (ref "CON1") (pin "63") (pinfunction "63_63") (pintype "bidirectional"))
      (node (ref "CON10") (pin "1") (pinfunction "1_1") (pintype "bidirectional"))
      (node (ref "CON11") (pin "1") (pinfunction "1_1") (pintype "bidirectional"))
      (node (ref "CON12") (pin "1") (pinfunction "1_1") (pintype "bidirectional"))
      (node (ref "CON13") (pin "2") (pinfunction "2_2") (pintype "bidirectional"))
      (node (ref "CON15") (pin "2") (pinfunction "2_2") (pintype "passive"))
      (node (ref "CON17") (pin "2") (pinfunction "2_2") (pintype "bidirectional"))
      (node (ref "CON2") (pin "2") (pinfunction "2_2") (pintype "bidirectional"))
      (node (ref "CON20") (pin "1") (pinfunction "1_1") (pintype "bidirectional"))
      (node (ref "CON21") (pin "1") (pinfunction "1_1") (pintype "bidirectional"))
      (node (ref "CON4") (pin "2") (pinfunction "2_2") (pintype "bidirectional"))
      (node (ref "CON6") (pin "1") (pinfunction "1_1") (pintype "bidirectional"))
      (node (ref "CON7") (pin "1") (pinfunction "1_1") (pintype "bidirectional"))
      (node (ref "CON8") (pin "1") (pinfunction "1_1") (pintype "bidirectional"))
      (node (ref "CON9") (pin "1") (pinfunction "1_1") (pintype "bidirectional"))
      (node (ref "D1") (pin "C") (pinfunction "C_C") (pintype "passive"))
      (node (ref "IC1") (pin "5") (pinfunction "V+_5") (pintype "bidirectional"))
      (node (ref "PAD3") (pin "P$1") (pinfunction "P$1_P$1") (pintype "bidirectional"))
      (node (ref "R16") (pin "1") (pinfunction "1_1") (pintype "passive"))
      (node (ref "R18") (pin "1") (pinfunction "1_1") (pintype "passive"))
      (node (ref "SJ1") (pin "2") (pinfunction "2_2") (pintype "passive"))
    )
    (net (code "111") (name "VDD_12V") (class "Default")
      (node (ref "C61") (pin "2") (pinfunction "2_2") (pintype "passive"))
      (node (ref "C62") (pin "2") (pinfunction "2_2") (pintype "passive"))
      (node (ref "C63") (pin "2") (pinfunction "2_2") (pintype "passive"))
      (node (ref "CON3") (pin "2") (pinfunction "2_2") (pintype "bidirectional"))
      (node (ref "CON3") (pin "3") (pinfunction "3_3") (pintype "bidirectional"))
      (node (ref "L7") (pin "2") (pinfunction "2_2") (pintype "bidirectional"))
      (node (ref "PAD15") (pin "P$1") (pinfunction "P$1_P$1") (pintype "bidirectional"))
      (node (ref "R41") (pin "2") (pinfunction "2_2") (pintype "passive"))
      (node (ref "R7") (pin "1") (pinfunction "1_1") (pintype "passive"))
    )
    (net (code "112") (name "VDD_24V") (class "Default")
      (node (ref "C16") (pin "P$2") (pinfunction "2_P$2") (pintype "passive"))
      (node (ref "C17") (pin "P$2") (pinfunction "2_P$2") (pintype "passive"))
      (node (ref "C18") (pin "P$2") (pinfunction "2_P$2") (pintype "passive"))
      (node (ref "CON18") (pin "10") (pinfunction "10_10") (pintype "passive"))
      (node (ref "CON18") (pin "11") (pinfunction "11_11") (pintype "passive"))
      (node (ref "CON18") (pin "9") (pinfunction "9_9") (pintype "passive"))
      (node (ref "L4") (pin "2") (pinfunction "2_2") (pintype "bidirectional"))
      (node (ref "PAD17") (pin "P$1") (pinfunction "P$1_P$1") (pintype "bidirectional"))
      (node (ref "R11") (pin "2") (pinfunction "2_2") (pintype "passive"))
      (node (ref "R8") (pin "1") (pinfunction "1_1") (pintype "passive"))
    )
    (net (code "113") (name "VDD_SERVO") (class "Default")
      (node (ref "CON1") (pin "53") (pinfunction "53_53") (pintype "bidirectional"))
    )
    (net (code "114") (name "VDD_SERVO_IN") (class "Default")
      (node (ref "CON1") (pin "9") (pinfunction "9_9") (pintype "bidirectional"))
    )
    (net (code "115") (name "unconnected-(IC5-EN-Pad3)") (class "Default")
      (node (ref "IC5") (pin "3") (pinfunction "EN_3") (pintype "bidirectional"))
    )
    (net (code "116") (name "~{EXTERN_CS}") (class "Default")
      (node (ref "CON1") (pin "5") (pinfunction "5_5") (pintype "bidirectional"))
    )
    (net (code "117") (name "~{IO-LED_SAFET_PROT}") (class "Default")
      (node (ref "CON1") (pin "28") (pinfunction "28_28") (pintype "bidirectional"))
    )
    (net (code "118") (name "~{VBUS_VALID}") (class "Default")
      (node (ref "CON1") (pin "59") (pinfunction "59_59") (pintype "bidirectional"))
    )
    (net (code "119") (name "~{VDD_5V_HIPOWER_OC}") (class "Default")
      (node (ref "CON1") (pin "45") (pinfunction "45_45") (pintype "bidirectional"))
    )
    (net (code "120") (name "~{VDD_5V_PERIPH_EN}") (class "Default")
      (node (ref "CON1") (pin "27") (pinfunction "27_27") (pintype "bidirectional"))
    )
    (net (code "121") (name "~{VDD_5V_PERIPH_OC}") (class "Default")
      (node (ref "CON1") (pin "43") (pinfunction "43_43") (pintype "bidirectional"))
    )
    (net (code "122") (name "~{VDD_BACKUP_VALID}") (class "Default")
      (node (ref "CON1") (pin "57") (pinfunction "57_57") (pintype "bidirectional"))
    )
  )
)
